# FlexiCan.net
KiCad netlist of a schematic drawn in Altium Designer
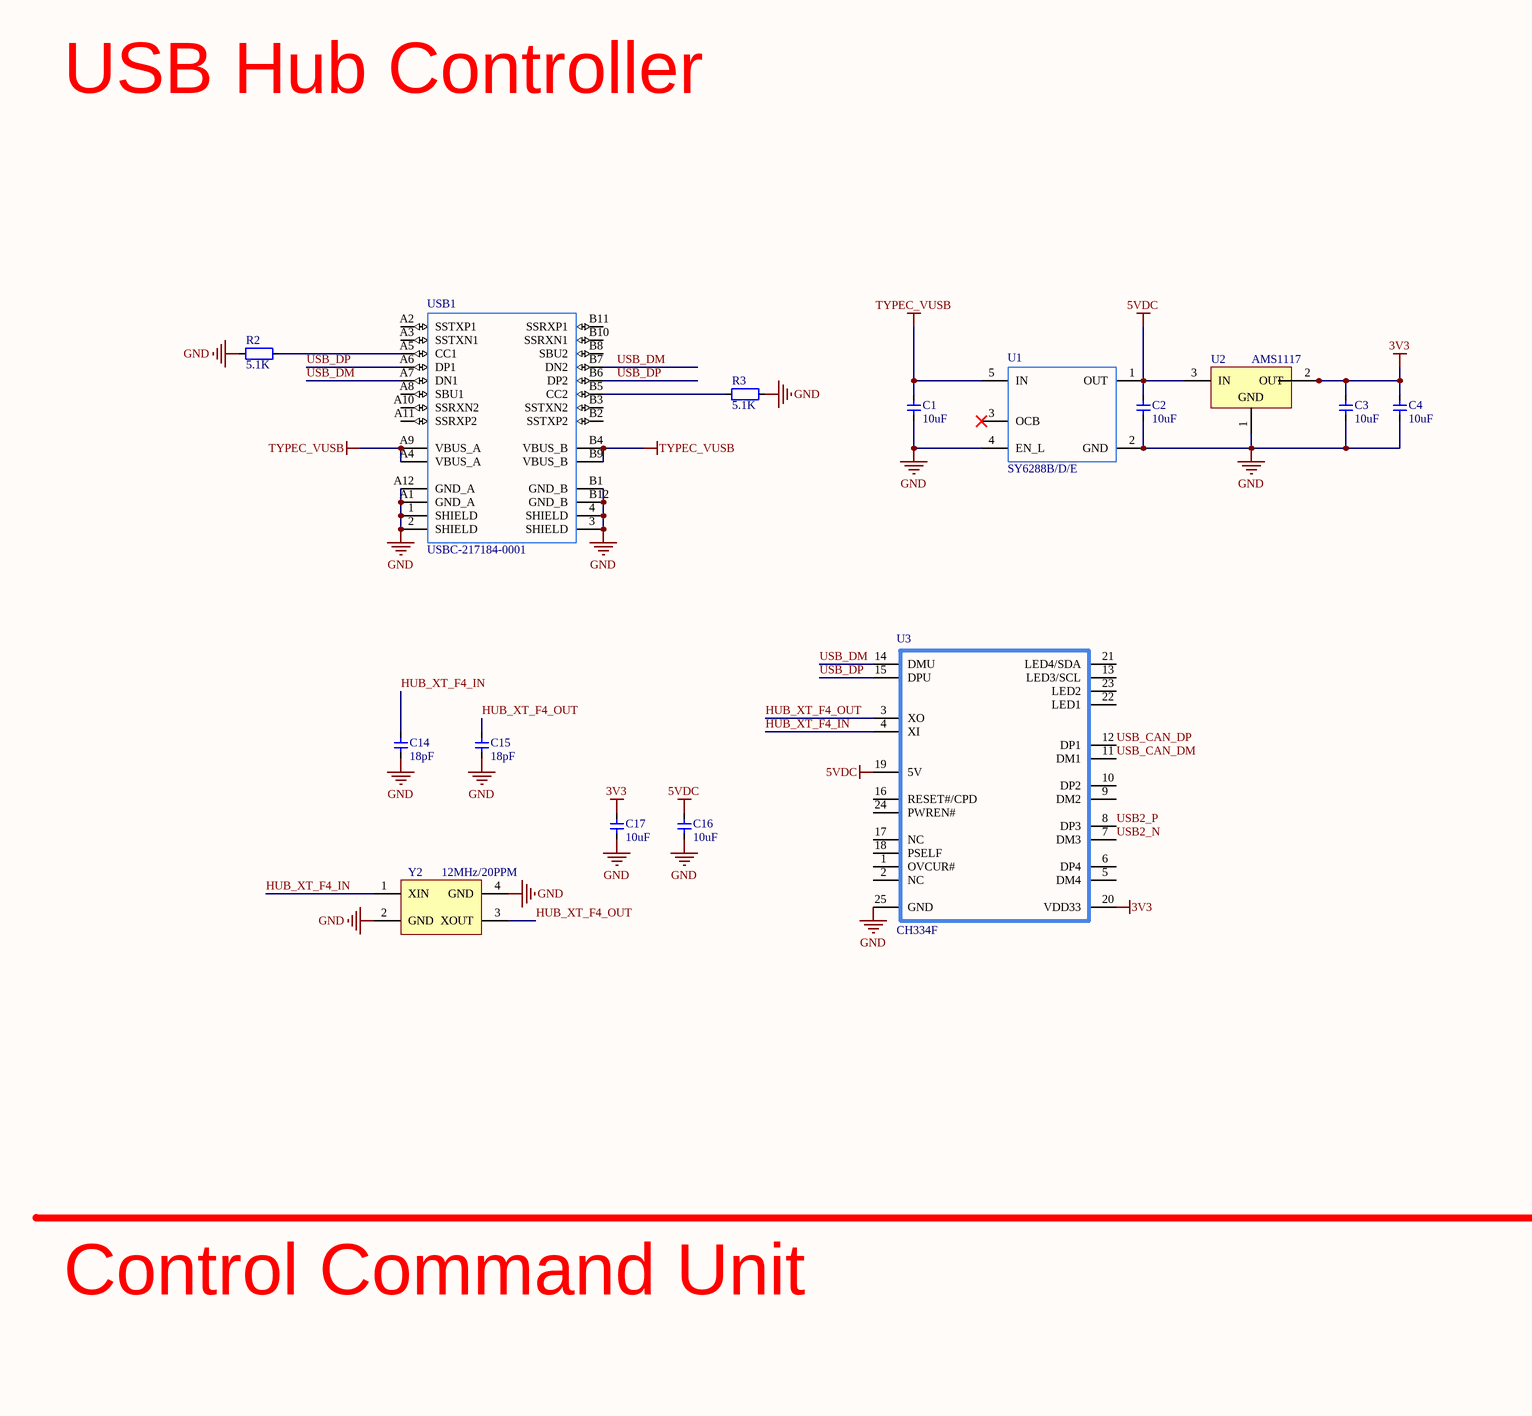
[diagram p0: FlexiCan.SchDoc, top left]
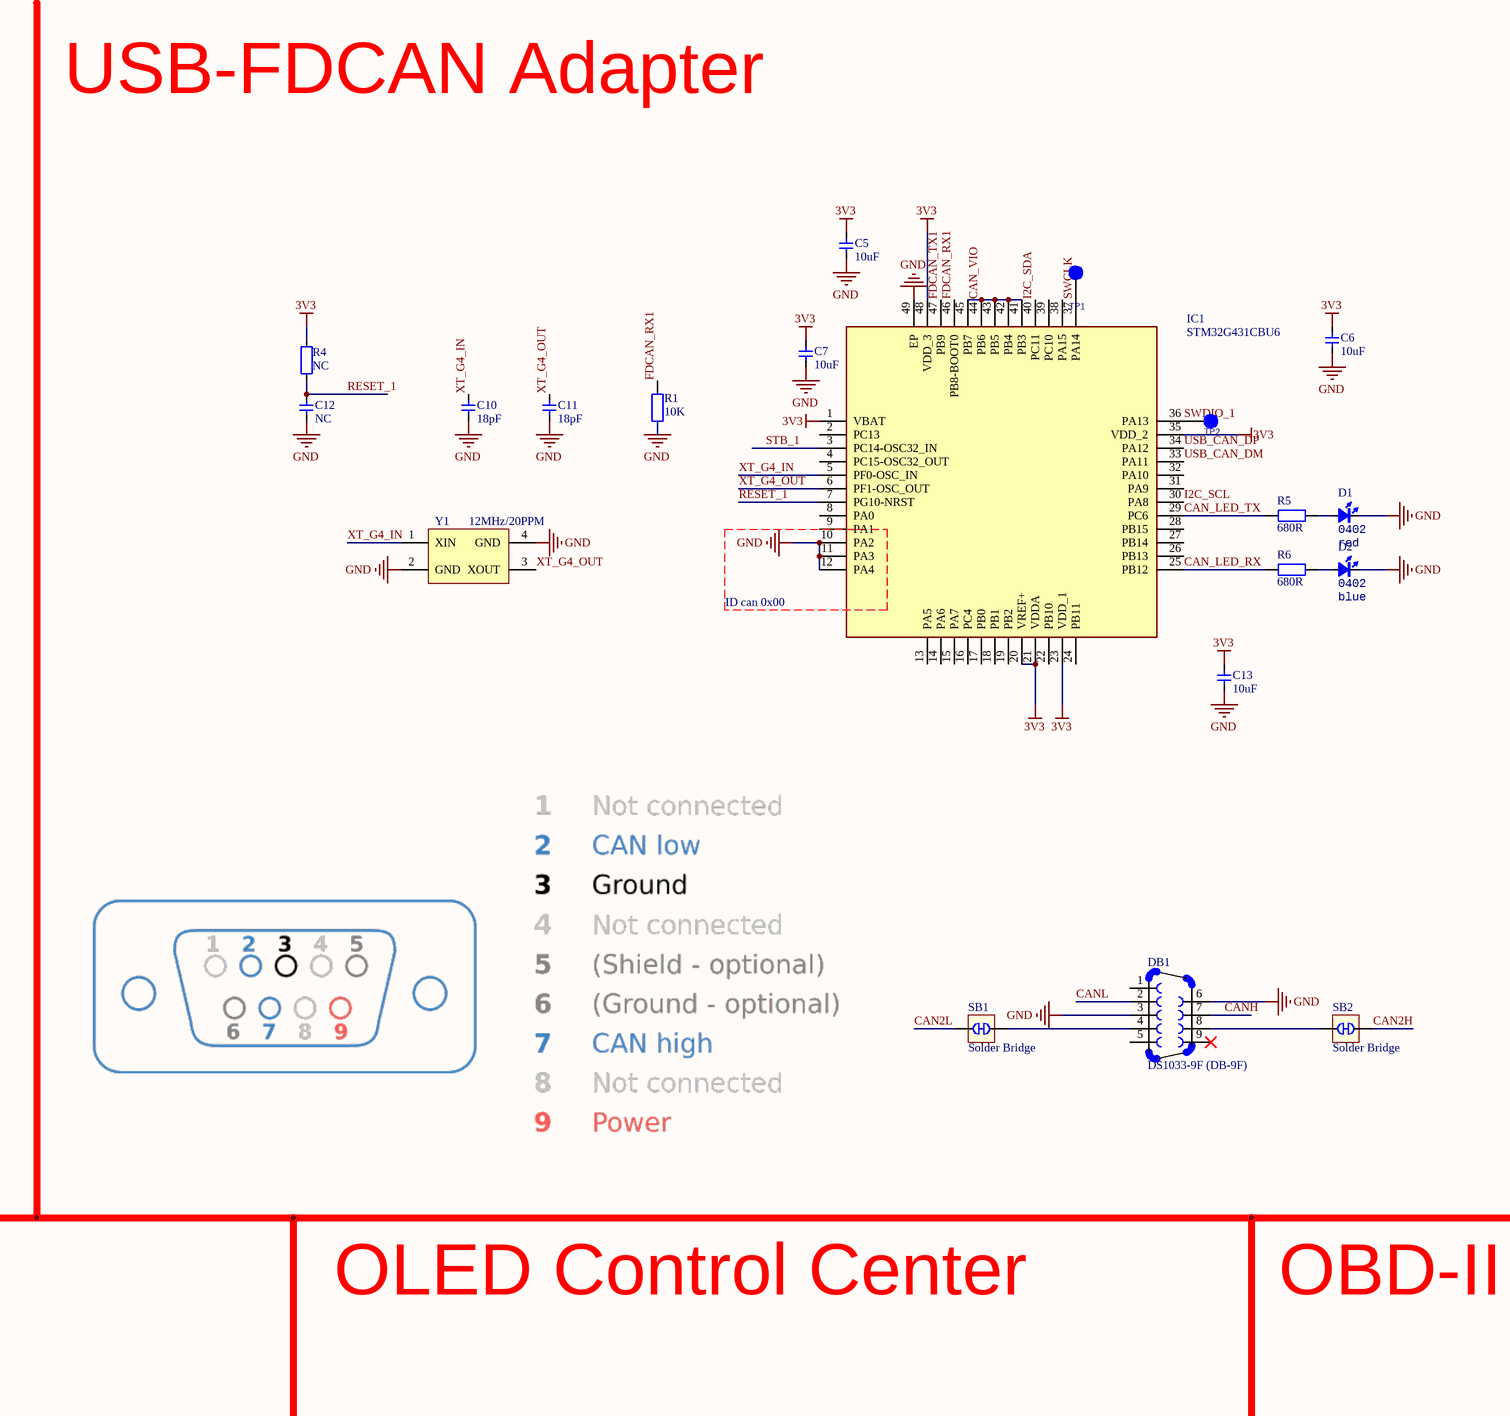
[diagram p1: FlexiCan.SchDoc, top middle]
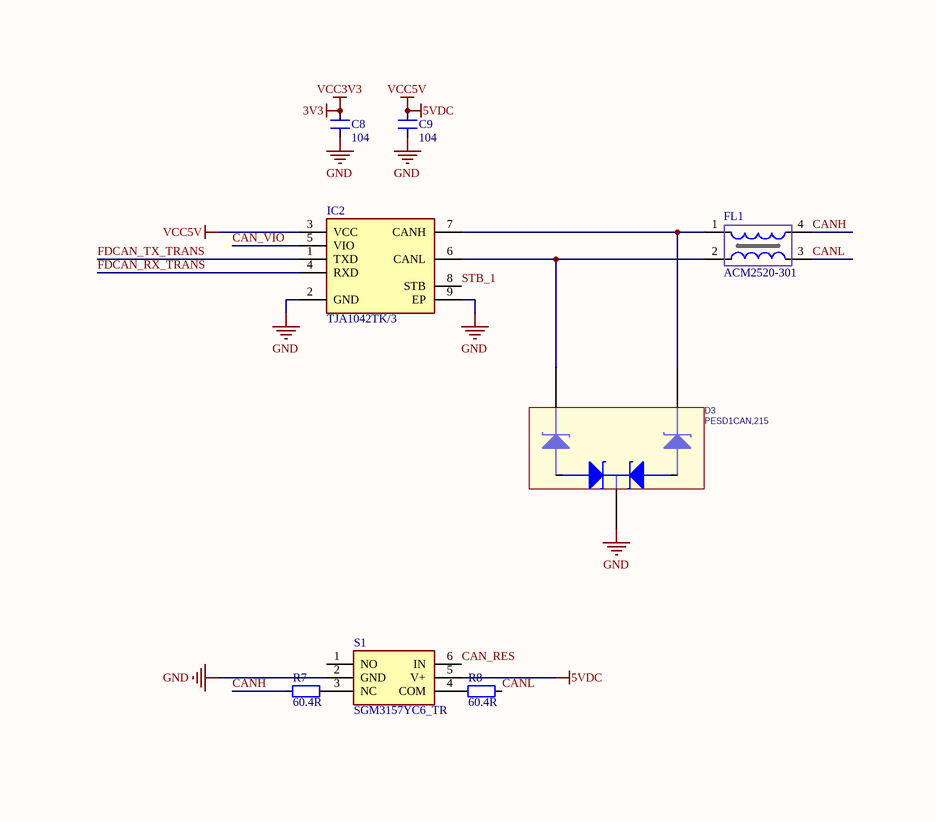
[diagram p2: FlexiCan.SchDoc, top right]
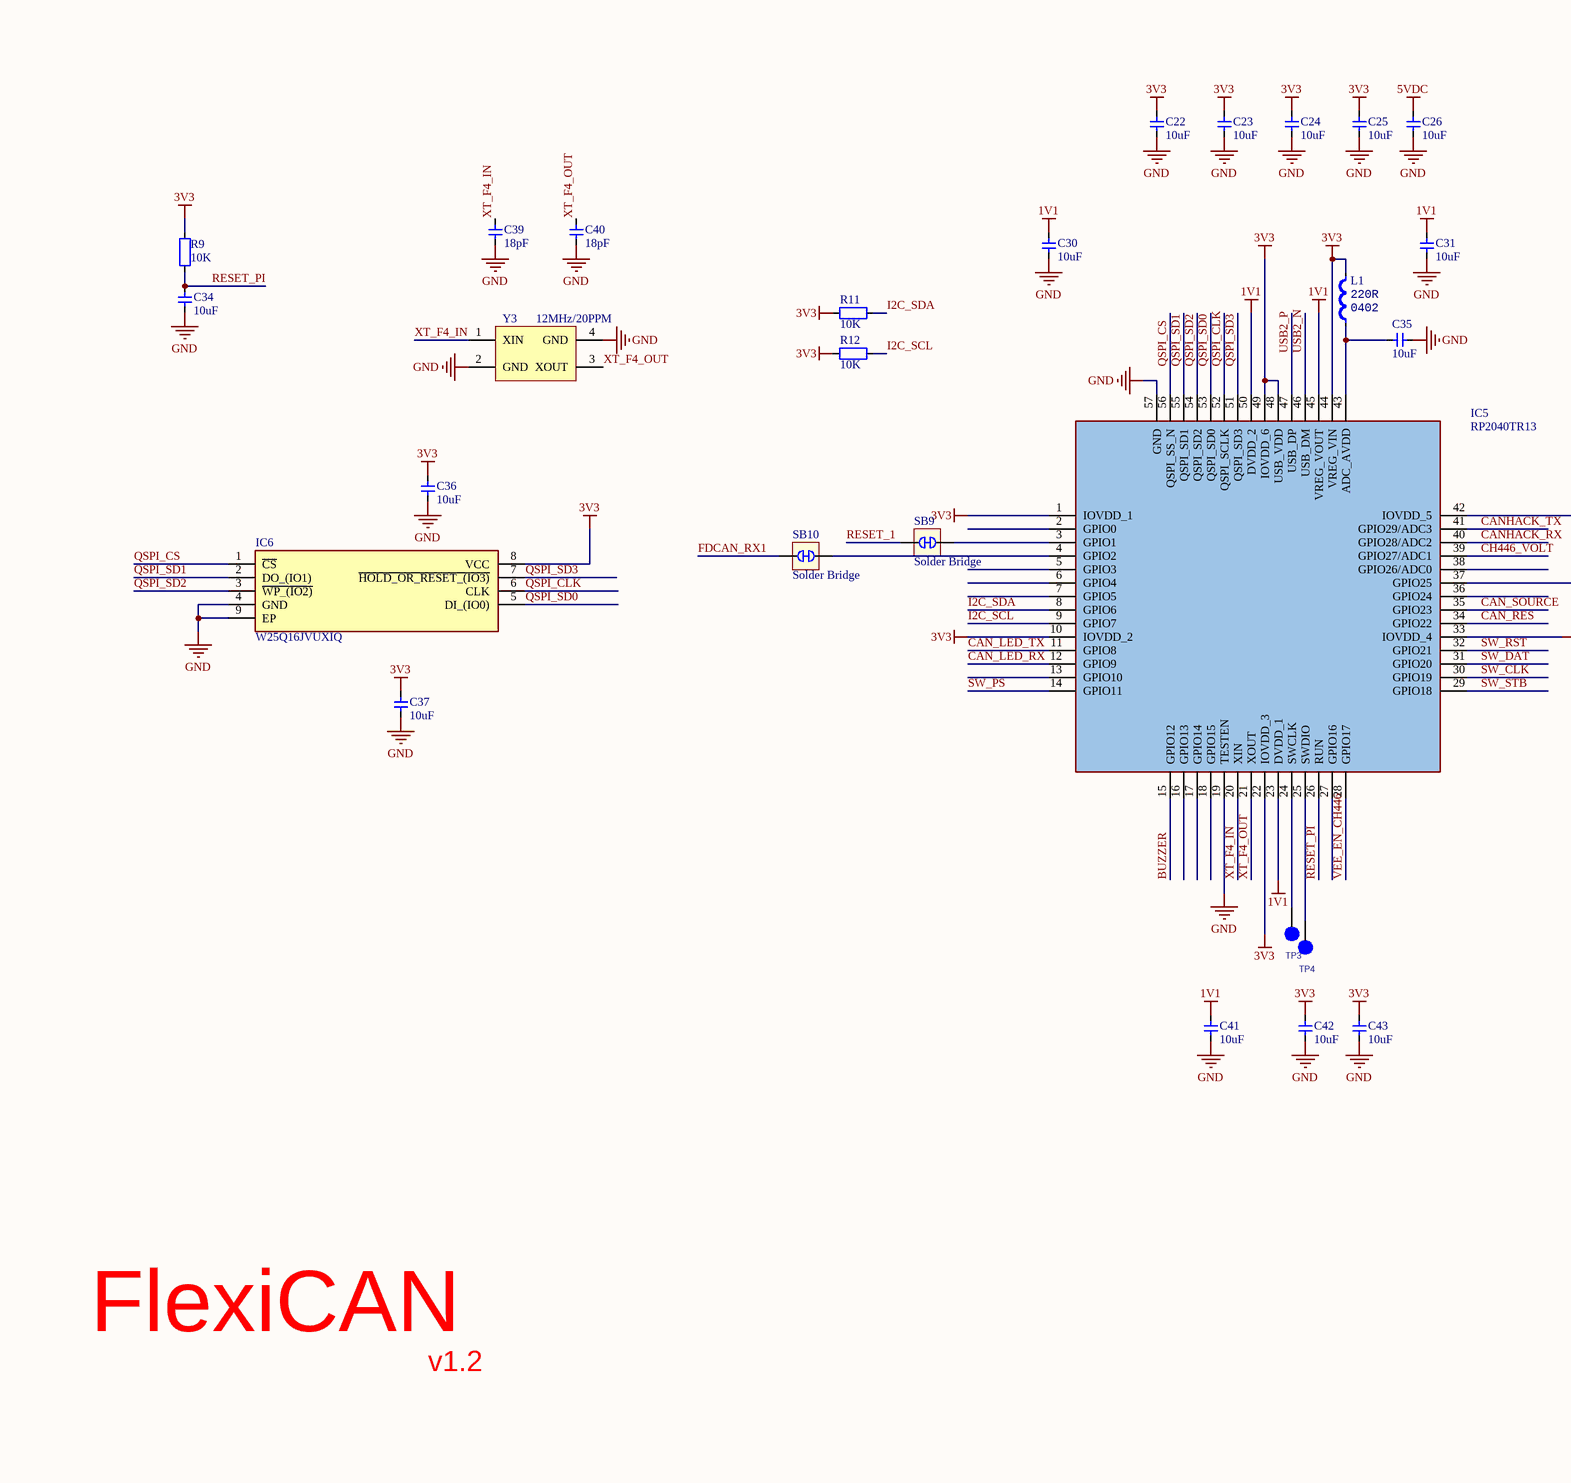
[diagram p3: FlexiCan.SchDoc, bottom left]
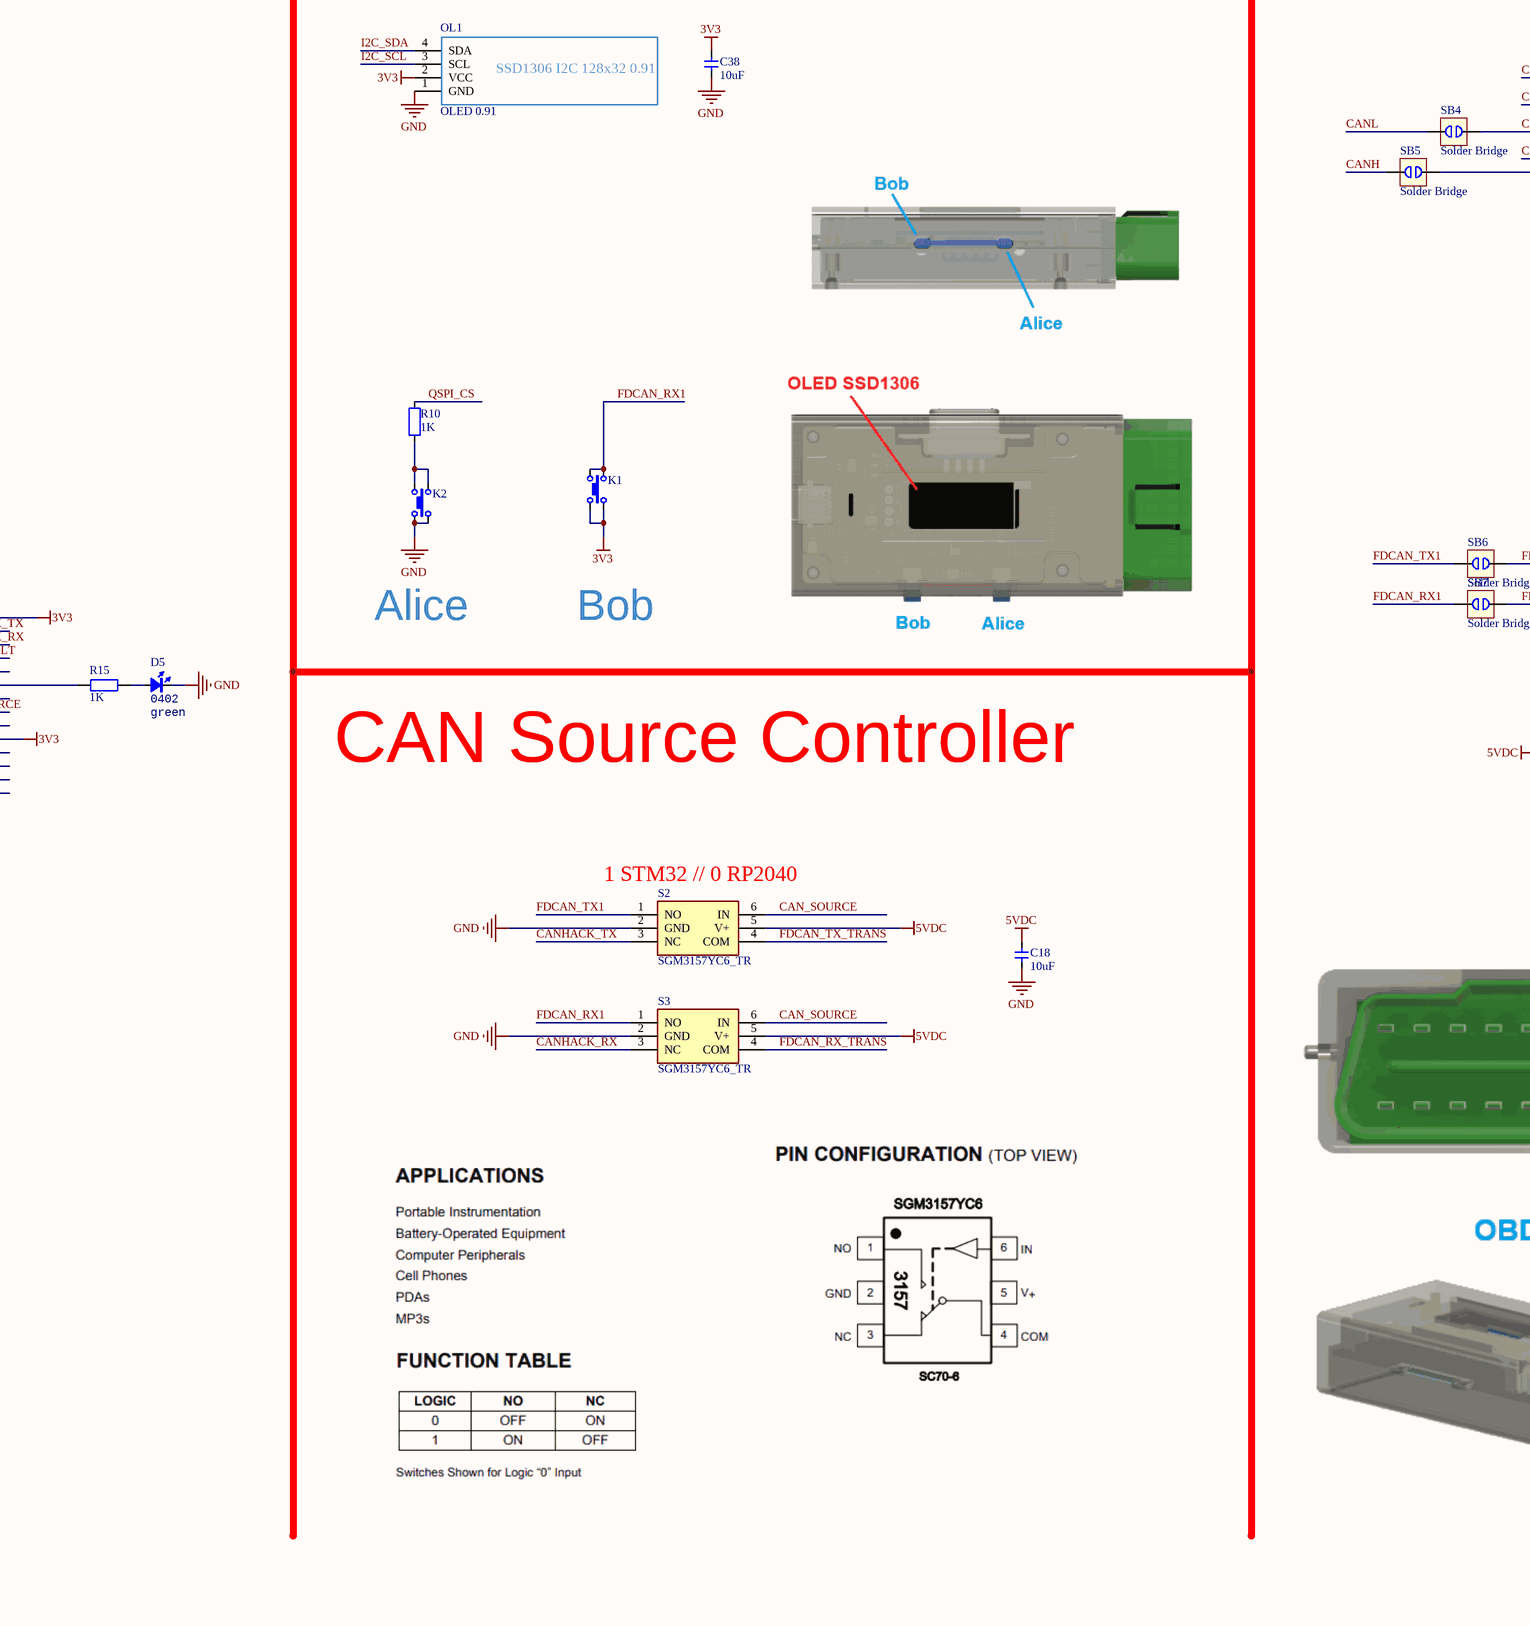
[diagram p4: FlexiCan.SchDoc, bottom middle]
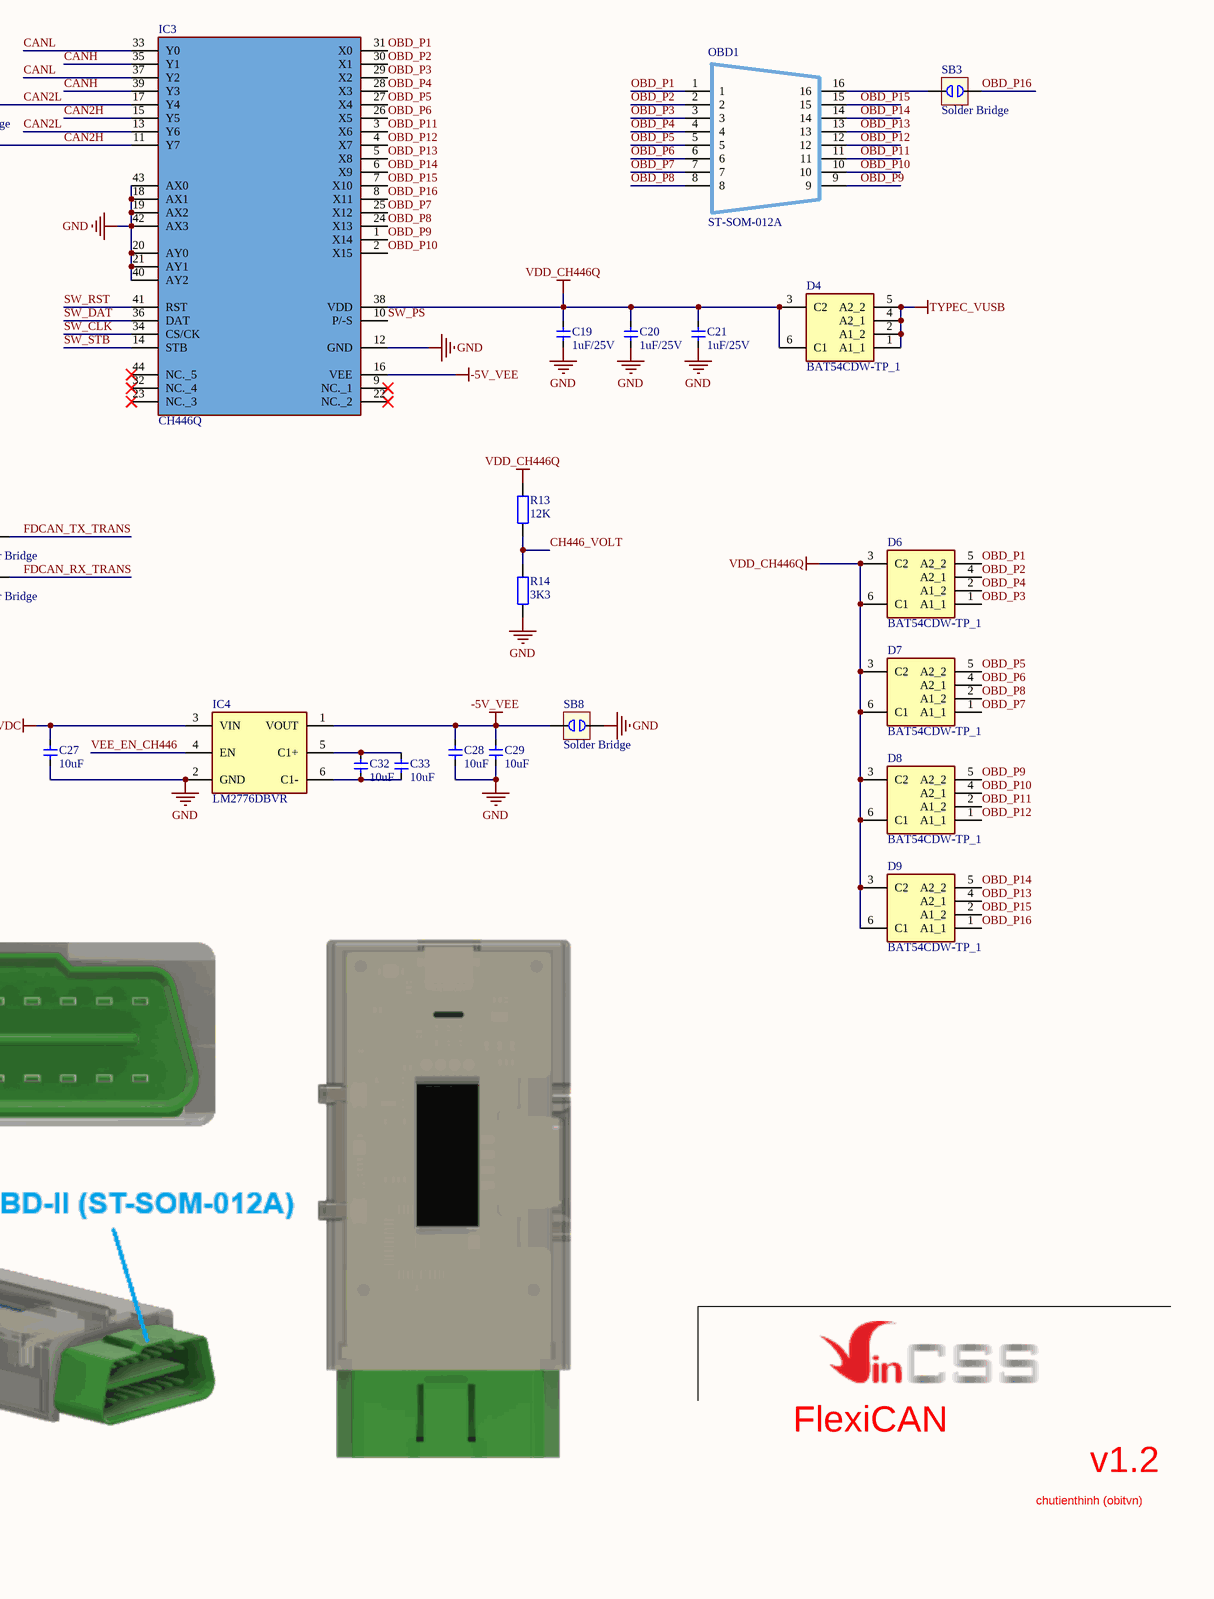
[diagram p5: FlexiCan.SchDoc, bottom right]

(export (version "E")
  (design (tool "Eeschema 10.0.6"))
  (components
    (comp (ref "C1")
      (value "10uF")
      (footprint "CAP_0402")
      (description "Capacitor")
      (libsource (lib "OBIT_TESLA") (part "C_0402"))
    )
    (comp (ref "C2")
      (value "10uF")
      (footprint "CAP_0402")
      (description "Capacitor")
      (libsource (lib "OBIT_TESLA") (part "C_0402"))
    )
    (comp (ref "C3")
      (value "10uF")
      (footprint "CAP_0402")
      (description "Capacitor")
      (libsource (lib "OBIT_TESLA") (part "C_0402"))
    )
    (comp (ref "C4")
      (value "10uF")
      (footprint "CAP_0402")
      (description "Capacitor")
      (libsource (lib "OBIT_TESLA") (part "C_0402"))
    )
    (comp (ref "C5")
      (value "10uF")
      (footprint "CAP_0402")
      (description "Capacitor")
      (libsource (lib "OBIT_TESLA") (part "C_0402"))
    )
    (comp (ref "C6")
      (value "10uF")
      (footprint "CAP_0402")
      (description "Capacitor")
      (libsource (lib "OBIT_TESLA") (part "C_0402"))
    )
    (comp (ref "C7")
      (value "10uF")
      (footprint "CAP_0402")
      (description "Capacitor")
      (libsource (lib "OBIT_TESLA") (part "C_0402"))
    )
    (comp (ref "C8")
      (value "104")
      (footprint "CAP_0402")
      (description "Cap SMD")
      (libsource (lib "OBIT_TESLA") (part "CM"))
    )
    (comp (ref "C9")
      (value "104")
      (footprint "CAP_0402")
      (description "Cap SMD")
      (libsource (lib "OBIT_TESLA") (part "CM"))
    )
    (comp (ref "C10")
      (value "18pF")
      (footprint "CAP_0402")
      (description "Capacitor")
      (libsource (lib "OBIT_TESLA") (part "C_0402"))
    )
    (comp (ref "C11")
      (value "18pF")
      (footprint "CAP_0402")
      (description "Capacitor")
      (libsource (lib "OBIT_TESLA") (part "C_0402"))
    )
    (comp (ref "C12")
      (value "NC")
      (footprint "CAP_0402")
      (description "Capacitor")
      (libsource (lib "OBIT_TESLA") (part "C_0402"))
    )
    (comp (ref "C13")
      (value "10uF")
      (footprint "CAP_0402")
      (description "Capacitor")
      (libsource (lib "OBIT_TESLA") (part "C_0402"))
    )
    (comp (ref "C14")
      (value "18pF")
      (footprint "CAP_0402")
      (description "Capacitor")
      (libsource (lib "OBIT_TESLA") (part "C_0402"))
    )
    (comp (ref "C15")
      (value "18pF")
      (footprint "CAP_0402")
      (description "Capacitor")
      (libsource (lib "OBIT_TESLA") (part "C_0402"))
    )
    (comp (ref "C16")
      (value "10uF")
      (footprint "CAP_0402")
      (description "Capacitor")
      (libsource (lib "OBIT_TESLA") (part "C_0402"))
    )
    (comp (ref "C17")
      (value "10uF")
      (footprint "CAP_0402")
      (description "Capacitor")
      (libsource (lib "OBIT_TESLA") (part "C_0402"))
    )
    (comp (ref "C18")
      (value "10uF")
      (footprint "CAP_0402")
      (description "Capacitor")
      (libsource (lib "OBIT_TESLA") (part "C_0402"))
    )
    (comp (ref "C19")
      (value "1uF/25V")
      (footprint "CAP_0402")
      (description "Capacitor")
      (libsource (lib "OBIT_TESLA") (part "C_0402"))
    )
    (comp (ref "C20")
      (value "1uF/25V")
      (footprint "CAP_0402")
      (description "Capacitor")
      (libsource (lib "OBIT_TESLA") (part "C_0402"))
    )
    (comp (ref "C21")
      (value "1uF/25V")
      (footprint "CAP_0402")
      (description "Capacitor")
      (libsource (lib "OBIT_TESLA") (part "C_0402"))
    )
    (comp (ref "C22")
      (value "10uF")
      (footprint "CAP_0402")
      (description "Capacitor")
      (libsource (lib "OBIT_TESLA") (part "C_0402"))
    )
    (comp (ref "C23")
      (value "10uF")
      (footprint "CAP_0402")
      (description "Capacitor")
      (libsource (lib "OBIT_TESLA") (part "C_0402"))
    )
    (comp (ref "C24")
      (value "10uF")
      (footprint "CAP_0402")
      (description "Capacitor")
      (libsource (lib "OBIT_TESLA") (part "C_0402"))
    )
    (comp (ref "C25")
      (value "10uF")
      (footprint "CAP_0402")
      (description "Capacitor")
      (libsource (lib "OBIT_TESLA") (part "C_0402"))
    )
    (comp (ref "C26")
      (value "10uF")
      (footprint "CAP_0402")
      (description "Capacitor")
      (libsource (lib "OBIT_TESLA") (part "C_0402"))
    )
    (comp (ref "C27")
      (value "10uF")
      (footprint "CAP_0402")
      (description "Capacitor")
      (libsource (lib "OBIT_TESLA") (part "C_0402"))
    )
    (comp (ref "C28")
      (value "10uF")
      (footprint "CAP_0402")
      (description "Capacitor")
      (libsource (lib "OBIT_TESLA") (part "C_0402"))
    )
    (comp (ref "C29")
      (value "10uF")
      (footprint "CAP_0402")
      (description "Capacitor")
      (libsource (lib "OBIT_TESLA") (part "C_0402"))
    )
    (comp (ref "C30")
      (value "10uF")
      (footprint "CAP_0402")
      (description "Capacitor")
      (libsource (lib "OBIT_TESLA") (part "C_0402"))
    )
    (comp (ref "C31")
      (value "10uF")
      (footprint "CAP_0402")
      (description "Capacitor")
      (libsource (lib "OBIT_TESLA") (part "C_0402"))
    )
    (comp (ref "C32")
      (value "10uF")
      (footprint "CAP_0402")
      (description "Capacitor")
      (libsource (lib "OBIT_TESLA") (part "C_0402"))
    )
    (comp (ref "C33")
      (value "10uF")
      (footprint "CAP_0402")
      (description "Capacitor")
      (libsource (lib "OBIT_TESLA") (part "C_0402"))
    )
    (comp (ref "C34")
      (value "10uF")
      (footprint "CAP_0402")
      (description "Capacitor")
      (libsource (lib "OBIT_TESLA") (part "C_0402"))
    )
    (comp (ref "C35")
      (value "10uF")
      (footprint "CAP_0402")
      (description "Capacitor")
      (libsource (lib "OBIT_TESLA") (part "C_0402"))
    )
    (comp (ref "C36")
      (value "10uF")
      (footprint "CAP_0402")
      (description "Capacitor")
      (libsource (lib "OBIT_TESLA") (part "C_0402"))
    )
    (comp (ref "C37")
      (value "10uF")
      (footprint "CAP_0402")
      (description "Capacitor")
      (libsource (lib "OBIT_TESLA") (part "C_0402"))
    )
    (comp (ref "C38")
      (value "10uF")
      (footprint "CAP_0402")
      (description "Capacitor")
      (libsource (lib "OBIT_TESLA") (part "C_0402"))
    )
    (comp (ref "C39")
      (value "18pF")
      (footprint "CAP_0402")
      (description "Capacitor")
      (libsource (lib "OBIT_TESLA") (part "C_0402"))
    )
    (comp (ref "C40")
      (value "18pF")
      (footprint "CAP_0402")
      (description "Capacitor")
      (libsource (lib "OBIT_TESLA") (part "C_0402"))
    )
    (comp (ref "C41")
      (value "10uF")
      (footprint "CAP_0402")
      (description "Capacitor")
      (libsource (lib "OBIT_TESLA") (part "C_0402"))
    )
    (comp (ref "C42")
      (value "10uF")
      (footprint "CAP_0402")
      (description "Capacitor")
      (libsource (lib "OBIT_TESLA") (part "C_0402"))
    )
    (comp (ref "C43")
      (value "10uF")
      (footprint "CAP_0402")
      (description "Capacitor")
      (libsource (lib "OBIT_TESLA") (part "C_0402"))
    )
    (comp (ref "D1")
      (value "red")
      (footprint "LED_0402_RED")
      (description "LED")
      (fields (field (name "TYPE") "0402"))
      (libsource (lib "OBIT_TESLA") (part "LED_0402"))
    )
    (comp (ref "D2")
      (value "blue")
      (footprint "LED_0402_BLUE")
      (description "LED")
      (fields (field (name "TYPE") "0402"))
      (libsource (lib "OBIT_TESLA") (part "LED_0402"))
    )
    (comp (ref "D3")
      (value "PESD1CAN,215")
      (footprint "SOT23-3")
      (description "TVS DIODE 5V 14V SOT23")
      (fields
        (field (name "MANUFACTURER PART #") "PESD5V0S2BT,215")
        (field (name "MANUFACTURER") "Nexperia USA Inc.")
        (field (name "CREATED BY") "eteofilo")
        (field (name "MODIFIED BY") "*")
      )
      (libsource (lib "OBIT_TESLA") (part "PESD5V0S2BT,215"))
    )
    (comp (ref "D4")
      (value "BAT54CDW-TP_1")
      (footprint "SOT65P222X120-6N")
      (description "Schottky Diode")
      (fields
        (field (name "MANUFACTURER_PART_NUMBER") "BAT54CDW-TP")
        (field (name "MOUSER PART NUMBER") "833-BAT54CDW-TP")
      )
      (libsource (lib "OBIT_TESLA") (part "BAT54CDW-TP_1"))
    )
    (comp (ref "D5")
      (value "green")
      (footprint "LED_0402_GREEN")
      (description "LED")
      (fields (field (name "TYPE") "0402"))
      (libsource (lib "OBIT_TESLA") (part "LED_0402"))
    )
    (comp (ref "D6")
      (value "BAT54CDW-TP_1")
      (footprint "SOT65P222X120-6N")
      (description "Schottky Diode")
      (fields
        (field (name "MANUFACTURER_PART_NUMBER") "BAT54CDW-TP")
        (field (name "MOUSER PART NUMBER") "833-BAT54CDW-TP")
      )
      (libsource (lib "OBIT_TESLA") (part "BAT54CDW-TP_1"))
    )
    (comp (ref "D7")
      (value "BAT54CDW-TP_1")
      (footprint "SOT65P222X120-6N")
      (description "Schottky Diode")
      (fields
        (field (name "MANUFACTURER_PART_NUMBER") "BAT54CDW-TP")
        (field (name "MOUSER PART NUMBER") "833-BAT54CDW-TP")
      )
      (libsource (lib "OBIT_TESLA") (part "BAT54CDW-TP_1"))
    )
    (comp (ref "D8")
      (value "BAT54CDW-TP_1")
      (footprint "SOT65P222X120-6N")
      (description "Schottky Diode")
      (fields
        (field (name "MANUFACTURER_PART_NUMBER") "BAT54CDW-TP")
        (field (name "MOUSER PART NUMBER") "833-BAT54CDW-TP")
      )
      (libsource (lib "OBIT_TESLA") (part "BAT54CDW-TP_1"))
    )
    (comp (ref "D9")
      (value "BAT54CDW-TP_1")
      (footprint "SOT65P222X120-6N")
      (description "Schottky Diode")
      (fields
        (field (name "MANUFACTURER_PART_NUMBER") "BAT54CDW-TP")
        (field (name "MOUSER PART NUMBER") "833-BAT54CDW-TP")
      )
      (libsource (lib "OBIT_TESLA") (part "BAT54CDW-TP_1"))
    )
    (comp (ref "DB1")
      (value "DS1033-9F (DB-9F)")
      (footprint "DB-9 DS1033-9F")
      (description "DS1033-9F (DB-9F) Female")
      (libsource (lib "OBIT_TESLA") (part "DB9-F"))
    )
    (comp (ref "FL1")
      (value "ACM2520-301")
      (footprint "ACM25203012P")
      (description "Common Mode Filters")
      (fields
        (field (name "MANUFACTURER_PART_NUMBER") "ACM9070-701-2PL-TL01")
        (field (name "MOUSER PART NUMBER") "810-ACM90707012PLTL")
      )
      (libsource (lib "OBIT_TESLA") (part "ACM2520-301-2PL-TL01_1"))
    )
    (comp (ref "IC1")
      (value "STM32G431CBU6")
      (footprint "QFN50P700X700X65-49N-D")
      (description "Integrated Circuit")
      (fields (field (name "MOUSER PART NUMBER") "511-STM32G431CBU6"))
      (libsource (lib "OBIT_TESLA") (part "STM32G431CBU6"))
    )
    (comp (ref "IC2")
      (value "TJA1042TK/3")
      (footprint "SON65P300X300X100-9N")
      (fields
        (field (name "MANUFACTURER_PART_NUMBER") "TJA1044VTKZ")
        (field (name "MOUSER PART NUMBER") "771-TJA1044VTKZ")
      )
      (libsource (lib "OBIT_TESLA") (part "SIT1044QTK/3"))
    )
    (comp (ref "IC3")
      (value "CH446Q")
      (footprint "QFP80P1350X1350X150-44N")
      (description "Integrated Circuit")
      (libsource (lib "OBIT_TESLA") (part "CH446Q"))
    )
    (comp (ref "IC4")
      (value "LM2776DBVR")
      (footprint "SOT95P280X145-6N")
      (description "Integrated Circuit")
      (fields (field (name "MOUSER PART NUMBER") "595-LM2776DBVR"))
      (libsource (lib "OBIT_TESLA") (part "LM2776DBVR"))
    )
    (comp (ref "IC5")
      (value "RP2040TR13")
      (footprint "RP2040TR13")
      (description "Integrated Circuit")
      (libsource (lib "OBIT_TESLA") (part "RP2040TR13"))
    )
    (comp (ref "IC6")
      (value "W25Q16JVUXIQ")
      (footprint "SON50P300X200X60-9N")
      (description "Integrated Circuit")
      (libsource (lib "OBIT_TESLA") (part "W25Q16JVUXIQ"))
    )
    (comp (ref "K1")
      (value "TACT 4P")
      (footprint "ButtonTACT_3.5*3.55_90")
      (description "Button")
      (libsource (lib "OBIT_TESLA") (part "ButtonTACT"))
    )
    (comp (ref "K2")
      (value "TACT 4P")
      (footprint "ButtonTACT_3.5*3.55_90")
      (description "Button")
      (libsource (lib "OBIT_TESLA") (part "ButtonTACT"))
    )
    (comp (ref "L1")
      (value "220R")
      (footprint "IND_0402Q")
      (description "Inductor")
      (fields (field (name "TYPE") "0402") (field (name "Comment") "H0402"))
      (libsource (lib "OBIT_TESLA") (part "Ind_0402"))
    )
    (comp (ref "OBD1")
      (value "ST-SOM-012A")
      (footprint "ST-SOM-012A")
      (description "ST-SOM-012A OBD II Connector")
      (libsource (lib "OBIT_TESLA") (part "ST-SOM-012A"))
    )
    (comp (ref "OL1")
      (value "OLED 0.91")
      (footprint "OLED 0.91 I2C")
      (description "HS HS91L02W2C01 \r\nSSD1306 I2C 128x32 0.91 - Organic Light Emitting Diode Display Screen ROHS")
      (libsource (lib "OBIT_TESLA") (part "OLED 0.91 128*32"))
    )
    (comp (ref "R1")
      (value "10K")
      (footprint "RES_0402")
      (description "Resistor R1/4W")
      (libsource (lib "OBIT_TESLA") (part "R"))
    )
    (comp (ref "R2")
      (value "5.1K")
      (footprint "RES_0402")
      (description "Resistor")
      (libsource (lib "OBIT_TESLA") (part "R-0402"))
    )
    (comp (ref "R3")
      (value "5.1K")
      (footprint "RES_0402")
      (description "Resistor")
      (libsource (lib "") (part "R-0402_1"))
    )
    (comp (ref "R4")
      (value "NC")
      (footprint "RES_0402")
      (description "Resistor")
      (libsource (lib "") (part "R-0402_2"))
    )
    (comp (ref "R5")
      (value "680R")
      (footprint "RES_0402")
      (description "Resistor R1/4W")
      (libsource (lib "OBIT_TESLA") (part "R"))
    )
    (comp (ref "R6")
      (value "680R")
      (footprint "RES_0402")
      (description "Resistor R1/4W")
      (libsource (lib "OBIT_TESLA") (part "R"))
    )
    (comp (ref "R7")
      (value "60.4R")
      (footprint "RES_0402")
      (description "Resistor")
      (libsource (lib "OBIT_TESLA") (part "R-0402"))
    )
    (comp (ref "R8")
      (value "60.4R")
      (footprint "RES_0402")
      (description "Resistor")
      (libsource (lib "OBIT_TESLA") (part "R-0402"))
    )
    (comp (ref "R9")
      (value "10K")
      (footprint "RES_0402")
      (description "Resistor")
      (libsource (lib "") (part "R-0402_2"))
    )
    (comp (ref "R10")
      (value "1K")
      (footprint "RES_0402")
      (description "Resistor")
      (libsource (lib "") (part "R-0402_3"))
    )
    (comp (ref "R11")
      (value "10K")
      (footprint "RES_0402")
      (description "Resistor")
      (libsource (lib "") (part "R-0402_1"))
    )
    (comp (ref "R12")
      (value "10K")
      (footprint "RES_0402")
      (description "Resistor")
      (libsource (lib "") (part "R-0402_1"))
    )
    (comp (ref "R13")
      (value "12K")
      (footprint "RES_0402")
      (description "Resistor R1/4W")
      (libsource (lib "OBIT_TESLA") (part "R"))
    )
    (comp (ref "R14")
      (value "3K3")
      (footprint "RES_0402")
      (description "Resistor R1/4W")
      (libsource (lib "OBIT_TESLA") (part "R"))
    )
    (comp (ref "R15")
      (value "1K")
      (footprint "RES_0402")
      (description "Resistor R1/4W")
      (libsource (lib "OBIT_TESLA") (part "R"))
    )
    (comp (ref "S1")
      (value "SGM3157YC6_TR")
      (footprint "SOT65P230X110-6N")
      (description "Switch")
      (fields (field (name "MANUFACTURER_PART_NUMBER") "SGM3157YC6/TR"))
      (libsource (lib "OBIT_TESLA") (part "SGM3157YC6_TR"))
    )
    (comp (ref "S2")
      (value "SGM3157YC6_TR")
      (footprint "SOT65P230X110-6N")
      (description "Switch")
      (fields (field (name "MANUFACTURER_PART_NUMBER") "SGM3157YC6/TR"))
      (libsource (lib "OBIT_TESLA") (part "SGM3157YC6_TR"))
    )
    (comp (ref "S3")
      (value "SGM3157YC6_TR")
      (footprint "SOT65P230X110-6N")
      (description "Switch")
      (fields (field (name "MANUFACTURER_PART_NUMBER") "SGM3157YC6/TR"))
      (libsource (lib "OBIT_TESLA") (part "SGM3157YC6_TR"))
    )
    (comp (ref "SB1")
      (value "Solder Bridge")
      (footprint "SB2_NC")
      (description "Solder Bridge 2")
      (libsource (lib "BYTECH_HW_LIB_2019") (part "SB 2 NC"))
    )
    (comp (ref "SB2")
      (value "Solder Bridge")
      (footprint "SB2_NC")
      (description "Solder Bridge 2")
      (libsource (lib "BYTECH_HW_LIB_2019") (part "SB 2 NC"))
    )
    (comp (ref "SB3")
      (value "Solder Bridge")
      (footprint "SB2_NO")
      (description "Solder Bridge 2")
      (libsource (lib "BYTECH_HW_LIB_2019") (part "SB 2 NO"))
    )
    (comp (ref "SB4")
      (value "Solder Bridge")
      (footprint "SB2_NO")
      (description "Solder Bridge 2")
      (libsource (lib "BYTECH_HW_LIB_2019") (part "SB 2 NO"))
    )
    (comp (ref "SB5")
      (value "Solder Bridge")
      (footprint "SB2_NO")
      (description "Solder Bridge 2")
      (libsource (lib "BYTECH_HW_LIB_2019") (part "SB 2 NO"))
    )
    (comp (ref "SB6")
      (value "Solder Bridge")
      (footprint "SB2_NO")
      (description "Solder Bridge 2")
      (libsource (lib "BYTECH_HW_LIB_2019") (part "SB 2 NO"))
    )
    (comp (ref "SB7")
      (value "Solder Bridge")
      (footprint "SB2_NO")
      (description "Solder Bridge 2")
      (libsource (lib "BYTECH_HW_LIB_2019") (part "SB 2 NO"))
    )
    (comp (ref "SB8")
      (value "Solder Bridge")
      (footprint "SB2_NO")
      (description "Solder Bridge 2")
      (libsource (lib "BYTECH_HW_LIB_2019") (part "SB 2 NO"))
    )
    (comp (ref "SB9")
      (value "Solder Bridge")
      (footprint "SB2_NC")
      (description "Solder Bridge 2")
      (libsource (lib "BYTECH_HW_LIB_2019") (part "SB 2 NC"))
    )
    (comp (ref "SB10")
      (value "Solder Bridge")
      (footprint "SB2_NC")
      (description "Solder Bridge 2")
      (libsource (lib "BYTECH_HW_LIB_2019") (part "SB 2 NC"))
    )
    (comp (ref "TP1")
      (value "TP 1mm")
      (footprint "SMT Test Point")
      (description "PCB TEST POINT SMT 1mm")
      (fields (field (name "MODIFIED BY") "*") (field (name "CREATED BY") "gmoreno"))
      (libsource (lib "") (part "TP 1mm_1"))
    )
    (comp (ref "TP2")
      (value "TP 1mm")
      (footprint "SMT Test Point")
      (description "PCB TEST POINT SMT 1mm")
      (fields (field (name "MODIFIED BY") "*") (field (name "CREATED BY") "gmoreno"))
      (libsource (lib "") (part "TP 1mm_2"))
    )
    (comp (ref "TP3")
      (value "TP 1mm")
      (footprint "SMT Test Point")
      (description "PCB TEST POINT SMT 1mm")
      (fields (field (name "MODIFIED BY") "*") (field (name "CREATED BY") "gmoreno"))
      (libsource (lib "OBIT_TESLA") (part "TP 1mm"))
    )
    (comp (ref "TP4")
      (value "TP 1mm")
      (footprint "SMT Test Point")
      (description "PCB TEST POINT SMT 1mm")
      (fields (field (name "MODIFIED BY") "*") (field (name "CREATED BY") "gmoreno"))
      (libsource (lib "OBIT_TESLA") (part "TP 1mm"))
    )
    (comp (ref "U1")
      (value "SY6288B/D/E")
      (footprint "SOT95P285X130-5N")
      (description "SY6288B/D/E Active Low")
      (libsource (lib "OBIT_TESLA") (part "SY6288_EN_L"))
    )
    (comp (ref "U2") (value "AMS1117") (footprint "SOT223") (libsource (lib "OBIT_TESLA") (part "AMS117")))
    (comp (ref "U3")
      (value "CH334F")
      (footprint "QFN50P400X400X80-25N-D")
      (description "CH334F Hub USB\r\nC5187527")
      (fields (field (name "JLCPCB PART #") "C5187527"))
      (libsource (lib "OBIT_TESLA") (part "CH334F"))
    )
    (comp (ref "USB1")
      (value "USBC-217184-0001")
      (footprint "Molex_217184-0001")
      (fields (field (name "MP") "USB4080-03-A") (field (name "MF") "Global Connector Technology"))
      (libsource (lib "OBIT_TESLA") (part "USBC-217184-0001"))
    )
    (comp (ref "Y1")
      (value "12MHz/20PPM")
      (footprint "XT-2520")
      (description "XT-2520")
      (fields (field (name "MF") "ECS International") (field (name "MP") "ECS-3225S30-240-EN-TR"))
      (libsource (lib "OBIT_TESLA") (part "XT-4Pin"))
    )
    (comp (ref "Y2")
      (value "12MHz/20PPM")
      (footprint "XT-2520")
      (description "XT-2520")
      (fields (field (name "MF") "ECS International") (field (name "MP") "ECS-3225S30-240-EN-TR"))
      (libsource (lib "OBIT_TESLA") (part "XT-4Pin"))
    )
    (comp (ref "Y3")
      (value "12MHz/20PPM")
      (footprint "XT-2520")
      (description "XT-2520")
      (fields (field (name "MF") "ECS International") (field (name "MP") "ECS-3225S30-240-EN-TR"))
      (libsource (lib "OBIT_TESLA") (part "XT-4Pin"))
    )
  )
  (nets
    (net (code "1") (name "-5V_VEE") (class "Default")
      (node (ref "C28") (pin "2") (pinfunction "2_2") (pintype "passive"))
      (node (ref "C29") (pin "2") (pinfunction "2_2") (pintype "passive"))
      (node (ref "IC3") (pin "16") (pinfunction "VEE_16") (pintype "passive"))
      (node (ref "IC4") (pin "1") (pinfunction "VOUT_1") (pintype "passive"))
      (node (ref "SB8") (pin "1") (pinfunction "1_1") (pintype "passive"))
    )
    (net (code "2") (name "/BUZZER") (class "Default")
      (node (ref "IC5") (pin "15") (pinfunction "GPIO12_15") (pintype "passive"))
    )
    (net (code "3") (name "/CAN2H") (class "Default")
      (node (ref "IC3") (pin "11") (pinfunction "Y7_11") (pintype "passive"))
      (node (ref "IC3") (pin "15") (pinfunction "Y5_15") (pintype "passive"))
      (node (ref "SB2") (pin "2") (pinfunction "2_2") (pintype "passive"))
      (node (ref "SB5") (pin "2") (pinfunction "2_2") (pintype "passive"))
    )
    (net (code "4") (name "/CAN2L") (class "Default")
      (node (ref "IC3") (pin "13") (pinfunction "Y6_13") (pintype "passive"))
      (node (ref "IC3") (pin "17") (pinfunction "Y4_17") (pintype "passive"))
      (node (ref "SB1") (pin "1") (pinfunction "1_1") (pintype "passive"))
      (node (ref "SB4") (pin "2") (pinfunction "2_2") (pintype "passive"))
    )
    (net (code "5") (name "/CANH") (class "Default")
      (node (ref "DB1") (pin "7") (pinfunction "7_7") (pintype "passive"))
      (node (ref "FL1") (pin "4") (pinfunction "4_4") (pintype "passive"))
      (node (ref "IC3") (pin "35") (pinfunction "Y1_35") (pintype "passive"))
      (node (ref "IC3") (pin "39") (pinfunction "Y3_39") (pintype "passive"))
      (node (ref "R7") (pin "1") (pinfunction "1_1") (pintype "passive"))
      (node (ref "SB5") (pin "1") (pinfunction "1_1") (pintype "passive"))
    )
    (net (code "6") (name "/CANHACK_RX") (class "Default")
      (node (ref "IC5") (pin "40") (pinfunction "GPIO28/ADC2_40") (pintype "passive"))
      (node (ref "S3") (pin "3") (pinfunction "NC_3") (pintype "passive"))
    )
    (net (code "7") (name "/CANHACK_TX") (class "Default")
      (node (ref "IC5") (pin "41") (pinfunction "GPIO29/ADC3_41") (pintype "passive"))
      (node (ref "S2") (pin "3") (pinfunction "NC_3") (pintype "passive"))
    )
    (net (code "8") (name "/CANL") (class "Default")
      (node (ref "DB1") (pin "2") (pinfunction "2_2") (pintype "passive"))
      (node (ref "FL1") (pin "3") (pinfunction "3_3") (pintype "passive"))
      (node (ref "IC3") (pin "33") (pinfunction "Y0_33") (pintype "passive"))
      (node (ref "IC3") (pin "37") (pinfunction "Y2_37") (pintype "passive"))
      (node (ref "R8") (pin "2") (pinfunction "2_2") (pintype "passive"))
      (node (ref "SB4") (pin "1") (pinfunction "1_1") (pintype "passive"))
    )
    (net (code "9") (name "/CAN_LED_RX") (class "Default")
      (node (ref "IC1") (pin "25") (pinfunction "PB12_25") (pintype "passive"))
      (node (ref "IC5") (pin "12") (pinfunction "GPIO9_12") (pintype "passive"))
      (node (ref "R6") (pin "1") (pinfunction "1_1") (pintype "passive"))
    )
    (net (code "10") (name "/CAN_LED_TX") (class "Default")
      (node (ref "IC1") (pin "29") (pinfunction "PC6_29") (pintype "passive"))
      (node (ref "IC5") (pin "11") (pinfunction "GPIO8_11") (pintype "passive"))
      (node (ref "R5") (pin "1") (pinfunction "1_1") (pintype "passive"))
    )
    (net (code "11") (name "/CAN_RES") (class "Default")
      (node (ref "IC5") (pin "34") (pinfunction "GPIO22_34") (pintype "passive"))
      (node (ref "S1") (pin "6") (pinfunction "IN_6") (pintype "passive"))
    )
    (net (code "12") (name "/CAN_SOURCE") (class "Default")
      (node (ref "IC5") (pin "35") (pinfunction "GPIO23_35") (pintype "passive"))
      (node (ref "S2") (pin "6") (pinfunction "IN_6") (pintype "passive"))
      (node (ref "S3") (pin "6") (pinfunction "IN_6") (pintype "passive"))
    )
    (net (code "13") (name "/CAN_VIO") (class "Default")
      (node (ref "IC1") (pin "41") (pinfunction "PB3_41") (pintype "passive"))
      (node (ref "IC1") (pin "42") (pinfunction "PB4_42") (pintype "passive"))
      (node (ref "IC1") (pin "43") (pinfunction "PB5_43") (pintype "passive"))
      (node (ref "IC1") (pin "44") (pinfunction "PB6_44") (pintype "passive"))
      (node (ref "IC1") (pin "45") (pinfunction "PB7_45") (pintype "passive"))
      (node (ref "IC2") (pin "5") (pinfunction "VIO_5") (pintype "passive"))
    )
    (net (code "14") (name "/CH446_VOLT") (class "Default")
      (node (ref "IC5") (pin "39") (pinfunction "GPIO27/ADC1_39") (pintype "passive"))
      (node (ref "R13") (pin "1") (pinfunction "1_1") (pintype "passive"))
      (node (ref "R14") (pin "2") (pinfunction "2_2") (pintype "passive"))
    )
    (net (code "15") (name "/FDCAN_RX1") (class "Default")
      (node (ref "IC1") (pin "46") (pinfunction "PB8-BOOT0_46") (pintype "passive"))
      (node (ref "K1") (pin "2") (pinfunction "2_2") (pintype "passive"))
      (node (ref "K1") (pin "4") (pinfunction "4_4") (pintype "passive"))
      (node (ref "R1") (pin "2") (pinfunction "2_2") (pintype "passive"))
      (node (ref "S3") (pin "1") (pinfunction "NO_1") (pintype "passive"))
      (node (ref "SB10") (pin "1") (pinfunction "1_1") (pintype "passive"))
      (node (ref "SB7") (pin "1") (pinfunction "1_1") (pintype "passive"))
    )
    (net (code "16") (name "/FDCAN_RX_TRANS") (class "Default")
      (node (ref "IC2") (pin "4") (pinfunction "RXD_4") (pintype "passive"))
      (node (ref "S3") (pin "4") (pinfunction "COM_4") (pintype "passive"))
      (node (ref "SB7") (pin "2") (pinfunction "2_2") (pintype "passive"))
    )
    (net (code "17") (name "/FDCAN_TX1") (class "Default")
      (node (ref "IC1") (pin "47") (pinfunction "PB9_47") (pintype "passive"))
      (node (ref "S2") (pin "1") (pinfunction "NO_1") (pintype "passive"))
      (node (ref "SB6") (pin "1") (pinfunction "1_1") (pintype "passive"))
    )
    (net (code "18") (name "/FDCAN_TX_TRANS") (class "Default")
      (node (ref "IC2") (pin "1") (pinfunction "TXD_1") (pintype "passive"))
      (node (ref "S2") (pin "4") (pinfunction "COM_4") (pintype "passive"))
      (node (ref "SB6") (pin "2") (pinfunction "2_2") (pintype "passive"))
    )
    (net (code "19") (name "/HUB_XT_F4_IN") (class "Default")
      (node (ref "C14") (pin "2") (pinfunction "2_2") (pintype "passive"))
      (node (ref "U3") (pin "4") (pinfunction "XI_4") (pintype "passive"))
      (node (ref "Y2") (pin "1") (pinfunction "XIN_1") (pintype "passive"))
    )
    (net (code "20") (name "/HUB_XT_F4_OUT") (class "Default")
      (node (ref "C15") (pin "2") (pinfunction "2_2") (pintype "passive"))
      (node (ref "U3") (pin "3") (pinfunction "XO_3") (pintype "passive"))
      (node (ref "Y2") (pin "3") (pinfunction "XOUT_3") (pintype "passive"))
    )
    (net (code "21") (name "/I2C_SCL") (class "Default")
      (node (ref "IC1") (pin "30") (pinfunction "PA8_30") (pintype "passive"))
      (node (ref "IC5") (pin "9") (pinfunction "GPIO7_9") (pintype "passive"))
      (node (ref "OL1") (pin "3") (pinfunction "SCL_3") (pintype "passive"))
      (node (ref "R12") (pin "1") (pinfunction "1_1") (pintype "passive"))
    )
    (net (code "22") (name "/I2C_SDA") (class "Default")
      (node (ref "IC1") (pin "40") (pinfunction "PC11_40") (pintype "passive"))
      (node (ref "IC5") (pin "8") (pinfunction "GPIO6_8") (pintype "passive"))
      (node (ref "OL1") (pin "4") (pinfunction "SDA_4") (pintype "passive"))
      (node (ref "R11") (pin "1") (pinfunction "1_1") (pintype "passive"))
    )
    (net (code "23") (name "/OBD_P1") (class "Default")
      (node (ref "D6") (pin "5") (pinfunction "A2_2_5") (pintype "passive"))
      (node (ref "IC3") (pin "31") (pinfunction "X0_31") (pintype "passive"))
      (node (ref "OBD1") (pin "1") (pinfunction "1_1") (pintype "passive"))
    )
    (net (code "24") (name "/OBD_P2") (class "Default")
      (node (ref "D6") (pin "4") (pinfunction "A2_1_4") (pintype "passive"))
      (node (ref "IC3") (pin "30") (pinfunction "X1_30") (pintype "passive"))
      (node (ref "OBD1") (pin "2") (pinfunction "2_2") (pintype "passive"))
    )
    (net (code "25") (name "/OBD_P3") (class "Default")
      (node (ref "D6") (pin "1") (pinfunction "A1_1_1") (pintype "passive"))
      (node (ref "IC3") (pin "29") (pinfunction "X2_29") (pintype "passive"))
      (node (ref "OBD1") (pin "3") (pinfunction "3_3") (pintype "passive"))
    )
    (net (code "26") (name "/OBD_P4") (class "Default")
      (node (ref "D6") (pin "2") (pinfunction "A1_2_2") (pintype "passive"))
      (node (ref "IC3") (pin "28") (pinfunction "X3_28") (pintype "passive"))
      (node (ref "OBD1") (pin "4") (pinfunction "4_4") (pintype "passive"))
    )
    (net (code "27") (name "/OBD_P5") (class "Default")
      (node (ref "D7") (pin "5") (pinfunction "A2_2_5") (pintype "passive"))
      (node (ref "IC3") (pin "27") (pinfunction "X4_27") (pintype "passive"))
      (node (ref "OBD1") (pin "5") (pinfunction "5_5") (pintype "passive"))
    )
    (net (code "28") (name "/OBD_P6") (class "Default")
      (node (ref "D7") (pin "4") (pinfunction "A2_1_4") (pintype "passive"))
      (node (ref "IC3") (pin "26") (pinfunction "X5_26") (pintype "passive"))
      (node (ref "OBD1") (pin "6") (pinfunction "6_6") (pintype "passive"))
    )
    (net (code "29") (name "/OBD_P7") (class "Default")
      (node (ref "D7") (pin "1") (pinfunction "A1_1_1") (pintype "passive"))
      (node (ref "IC3") (pin "25") (pinfunction "X12_25") (pintype "passive"))
      (node (ref "OBD1") (pin "7") (pinfunction "7_7") (pintype "passive"))
    )
    (net (code "30") (name "/OBD_P8") (class "Default")
      (node (ref "D7") (pin "2") (pinfunction "A1_2_2") (pintype "passive"))
      (node (ref "IC3") (pin "24") (pinfunction "X13_24") (pintype "passive"))
      (node (ref "OBD1") (pin "8") (pinfunction "8_8") (pintype "passive"))
    )
    (net (code "31") (name "/OBD_P9") (class "Default")
      (node (ref "D8") (pin "5") (pinfunction "A2_2_5") (pintype "passive"))
      (node (ref "IC3") (pin "1") (pinfunction "X14_1") (pintype "passive"))
      (node (ref "OBD1") (pin "9") (pinfunction "9_9") (pintype "passive"))
    )
    (net (code "32") (name "/OBD_P10") (class "Default")
      (node (ref "D8") (pin "4") (pinfunction "A2_1_4") (pintype "passive"))
      (node (ref "IC3") (pin "2") (pinfunction "X15_2") (pintype "passive"))
      (node (ref "OBD1") (pin "10") (pinfunction "10_10") (pintype "passive"))
    )
    (net (code "33") (name "/OBD_P11") (class "Default")
      (node (ref "D8") (pin "2") (pinfunction "A1_2_2") (pintype "passive"))
      (node (ref "IC3") (pin "3") (pinfunction "X6_3") (pintype "passive"))
      (node (ref "OBD1") (pin "11") (pinfunction "11_11") (pintype "passive"))
    )
    (net (code "34") (name "/OBD_P12") (class "Default")
      (node (ref "D8") (pin "1") (pinfunction "A1_1_1") (pintype "passive"))
      (node (ref "IC3") (pin "4") (pinfunction "X7_4") (pintype "passive"))
      (node (ref "OBD1") (pin "12") (pinfunction "12_12") (pintype "passive"))
    )
    (net (code "35") (name "/OBD_P13") (class "Default")
      (node (ref "D9") (pin "4") (pinfunction "A2_1_4") (pintype "passive"))
      (node (ref "IC3") (pin "5") (pinfunction "X8_5") (pintype "passive"))
      (node (ref "OBD1") (pin "13") (pinfunction "13_13") (pintype "passive"))
    )
    (net (code "36") (name "/OBD_P14") (class "Default")
      (node (ref "D9") (pin "5") (pinfunction "A2_2_5") (pintype "passive"))
      (node (ref "IC3") (pin "6") (pinfunction "X9_6") (pintype "passive"))
      (node (ref "OBD1") (pin "14") (pinfunction "14_14") (pintype "passive"))
    )
    (net (code "37") (name "/OBD_P15") (class "Default")
      (node (ref "D9") (pin "2") (pinfunction "A1_2_2") (pintype "passive"))
      (node (ref "IC3") (pin "7") (pinfunction "X10_7") (pintype "passive"))
      (node (ref "OBD1") (pin "15") (pinfunction "15_15") (pintype "passive"))
    )
    (net (code "38") (name "/OBD_P16") (class "Default")
      (node (ref "D9") (pin "1") (pinfunction "A1_1_1") (pintype "passive"))
      (node (ref "IC3") (pin "8") (pinfunction "X11_8") (pintype "passive"))
      (node (ref "SB3") (pin "2") (pinfunction "2_2") (pintype "passive"))
    )
    (net (code "39") (name "/QSPI_CLK") (class "Default")
      (node (ref "IC5") (pin "52") (pinfunction "QSPI_SCLK_52") (pintype "passive"))
      (node (ref "IC6") (pin "6") (pinfunction "CLK_6") (pintype "passive"))
    )
    (net (code "40") (name "/QSPI_CS") (class "Default")
      (node (ref "IC5") (pin "56") (pinfunction "QSPI_SS_N_56") (pintype "passive"))
      (node (ref "IC6") (pin "1") (pinfunction "~{CS}_1") (pintype "passive"))
      (node (ref "R10") (pin "1") (pinfunction "1_1") (pintype "passive"))
    )
    (net (code "41") (name "/QSPI_SD0") (class "Default")
      (node (ref "IC5") (pin "53") (pinfunction "QSPI_SD0_53") (pintype "passive"))
      (node (ref "IC6") (pin "5") (pinfunction "DI_(IO0)_5") (pintype "passive"))
    )
    (net (code "42") (name "/QSPI_SD1") (class "Default")
      (node (ref "IC5") (pin "55") (pinfunction "QSPI_SD1_55") (pintype "passive"))
      (node (ref "IC6") (pin "2") (pinfunction "DO_(IO1)_2") (pintype "passive"))
    )
    (net (code "43") (name "/QSPI_SD2") (class "Default")
      (node (ref "IC5") (pin "54") (pinfunction "QSPI_SD2_54") (pintype "passive"))
      (node (ref "IC6") (pin "3") (pinfunction "~{WP_(IO2)}_3") (pintype "passive"))
    )
    (net (code "44") (name "/QSPI_SD3") (class "Default")
      (node (ref "IC5") (pin "51") (pinfunction "QSPI_SD3_51") (pintype "passive"))
      (node (ref "IC6") (pin "7") (pinfunction "~{HOLD_OR_RESET_(IO3)}_7") (pintype "passive"))
    )
    (net (code "45") (name "/RESET_1") (class "Default")
      (node (ref "C12") (pin "2") (pinfunction "2_2") (pintype "passive"))
      (node (ref "IC1") (pin "7") (pinfunction "PG10-NRST_7") (pintype "passive"))
      (node (ref "R4") (pin "1") (pinfunction "1_1") (pintype "passive"))
      (node (ref "SB9") (pin "1") (pinfunction "1_1") (pintype "passive"))
    )
    (net (code "46") (name "/RESET_PI") (class "Default")
      (node (ref "C34") (pin "2") (pinfunction "2_2") (pintype "passive"))
      (node (ref "IC5") (pin "26") (pinfunction "RUN_26") (pintype "passive"))
      (node (ref "R9") (pin "1") (pinfunction "1_1") (pintype "passive"))
    )
    (net (code "47") (name "/STB_1") (class "Default")
      (node (ref "IC1") (pin "3") (pinfunction "PC14-OSC32_IN_3") (pintype "passive"))
      (node (ref "IC2") (pin "8") (pinfunction "STB_8") (pintype "passive"))
    )
    (net (code "48") (name "/SWCLK") (class "Default")
      (node (ref "IC1") (pin "37") (pinfunction "PA14_37") (pintype "passive"))
      (node (ref "TP1") (pin "1") (pinfunction "TP_1") (pintype "passive"))
    )
    (net (code "49") (name "/SWDIO_1") (class "Default")
      (node (ref "IC1") (pin "36") (pinfunction "PA13_36") (pintype "passive"))
      (node (ref "TP2") (pin "1") (pinfunction "TP_1") (pintype "passive"))
    )
    (net (code "50") (name "/SW_CLK") (class "Default")
      (node (ref "IC3") (pin "34") (pinfunction "CS/CK_34") (pintype "passive"))
      (node (ref "IC5") (pin "30") (pinfunction "GPIO19_30") (pintype "passive"))
    )
    (net (code "51") (name "/SW_DAT") (class "Default")
      (node (ref "IC3") (pin "36") (pinfunction "DAT_36") (pintype "passive"))
      (node (ref "IC5") (pin "31") (pinfunction "GPIO20_31") (pintype "passive"))
    )
    (net (code "52") (name "/SW_PS") (class "Default")
      (node (ref "IC3") (pin "10") (pinfunction "P/-S_10") (pintype "passive"))
      (node (ref "IC5") (pin "14") (pinfunction "GPIO11_14") (pintype "passive"))
    )
    (net (code "53") (name "/SW_RST") (class "Default")
      (node (ref "IC3") (pin "41") (pinfunction "RST_41") (pintype "passive"))
      (node (ref "IC5") (pin "32") (pinfunction "GPIO21_32") (pintype "passive"))
    )
    (net (code "54") (name "/SW_STB") (class "Default")
      (node (ref "IC3") (pin "14") (pinfunction "STB_14") (pintype "passive"))
      (node (ref "IC5") (pin "29") (pinfunction "GPIO18_29") (pintype "passive"))
    )
    (net (code "55") (name "/USB2_N") (class "Default")
      (node (ref "IC5") (pin "46") (pinfunction "USB_DM_46") (pintype "passive"))
      (node (ref "U3") (pin "7") (pinfunction "DM3_7") (pintype "passive"))
    )
    (net (code "56") (name "/USB2_P") (class "Default")
      (node (ref "IC5") (pin "47") (pinfunction "USB_DP_47") (pintype "passive"))
      (node (ref "U3") (pin "8") (pinfunction "DP3_8") (pintype "passive"))
    )
    (net (code "57") (name "/USB_CAN_DM") (class "Default")
      (node (ref "IC1") (pin "33") (pinfunction "PA11_33") (pintype "passive"))
      (node (ref "U3") (pin "11") (pinfunction "DM1_11") (pintype "passive"))
    )
    (net (code "58") (name "/USB_CAN_DP") (class "Default")
      (node (ref "IC1") (pin "34") (pinfunction "PA12_34") (pintype "passive"))
      (node (ref "U3") (pin "12") (pinfunction "DP1_12") (pintype "passive"))
    )
    (net (code "59") (name "/USB_DM") (class "Default")
      (node (ref "U3") (pin "14") (pinfunction "DMU_14") (pintype "passive"))
      (node (ref "USB1") (pin "A7") (pinfunction "DN1_A7") (pintype "bidirectional"))
      (node (ref "USB1") (pin "B7") (pinfunction "DN2_B7") (pintype "bidirectional"))
    )
    (net (code "60") (name "/USB_DP") (class "Default")
      (node (ref "U3") (pin "15") (pinfunction "DPU_15") (pintype "passive"))
      (node (ref "USB1") (pin "A6") (pinfunction "DP1_A6") (pintype "bidirectional"))
      (node (ref "USB1") (pin "B6") (pinfunction "DP2_B6") (pintype "bidirectional"))
    )
    (net (code "61") (name "/VEE_EN_CH446") (class "Default")
      (node (ref "IC4") (pin "4") (pinfunction "EN_4") (pintype "passive"))
      (node (ref "IC5") (pin "28") (pinfunction "GPIO17_28") (pintype "passive"))
    )
    (net (code "62") (name "/XT_F4_IN") (class "Default")
      (node (ref "C39") (pin "2") (pinfunction "2_2") (pintype "passive"))
      (node (ref "IC5") (pin "20") (pinfunction "XIN_20") (pintype "passive"))
      (node (ref "Y3") (pin "1") (pinfunction "XIN_1") (pintype "passive"))
    )
    (net (code "63") (name "/XT_F4_OUT") (class "Default")
      (node (ref "C40") (pin "2") (pinfunction "2_2") (pintype "passive"))
      (node (ref "IC5") (pin "21") (pinfunction "XOUT_21") (pintype "passive"))
      (node (ref "Y3") (pin "3") (pinfunction "XOUT_3") (pintype "passive"))
    )
    (net (code "64") (name "/XT_G4_IN") (class "Default")
      (node (ref "C10") (pin "2") (pinfunction "2_2") (pintype "passive"))
      (node (ref "IC1") (pin "5") (pinfunction "PF0-OSC_IN_5") (pintype "passive"))
      (node (ref "Y1") (pin "1") (pinfunction "XIN_1") (pintype "passive"))
    )
    (net (code "65") (name "/XT_G4_OUT") (class "Default")
      (node (ref "C11") (pin "2") (pinfunction "2_2") (pintype "passive"))
      (node (ref "IC1") (pin "6") (pinfunction "PF1-OSC_OUT_6") (pintype "passive"))
      (node (ref "Y1") (pin "3") (pinfunction "XOUT_3") (pintype "passive"))
    )
    (net (code "66") (name "1V1") (class "Default")
      (node (ref "C30") (pin "2") (pinfunction "2_2") (pintype "passive"))
      (node (ref "C31") (pin "2") (pinfunction "2_2") (pintype "passive"))
      (node (ref "C41") (pin "2") (pinfunction "2_2") (pintype "passive"))
      (node (ref "IC5") (pin "23") (pinfunction "DVDD_1_23") (pintype "passive"))
      (node (ref "IC5") (pin "45") (pinfunction "VREG_VOUT_45") (pintype "passive"))
      (node (ref "IC5") (pin "50") (pinfunction "DVDD_2_50") (pintype "passive"))
    )
    (net (code "67") (name "3V3") (class "Default")
      (node (ref "C13") (pin "2") (pinfunction "2_2") (pintype "passive"))
      (node (ref "C17") (pin "2") (pinfunction "2_2") (pintype "passive"))
      (node (ref "C22") (pin "2") (pinfunction "2_2") (pintype "passive"))
      (node (ref "C23") (pin "2") (pinfunction "2_2") (pintype "passive"))
      (node (ref "C24") (pin "2") (pinfunction "2_2") (pintype "passive"))
      (node (ref "C25") (pin "2") (pinfunction "2_2") (pintype "passive"))
      (node (ref "C3") (pin "2") (pinfunction "2_2") (pintype "passive"))
      (node (ref "C36") (pin "1") (pinfunction "1_1") (pintype "passive"))
      (node (ref "C37") (pin "2") (pinfunction "2_2") (pintype "passive"))
      (node (ref "C38") (pin "2") (pinfunction "2_2") (pintype "passive"))
      (node (ref "C4") (pin "2") (pinfunction "2_2") (pintype "passive"))
      (node (ref "C42") (pin "2") (pinfunction "2_2") (pintype "passive"))
      (node (ref "C43") (pin "2") (pinfunction "2_2") (pintype "passive"))
      (node (ref "C5") (pin "2") (pinfunction "2_2") (pintype "passive"))
      (node (ref "C6") (pin "2") (pinfunction "2_2") (pintype "passive"))
      (node (ref "C7") (pin "2") (pinfunction "2_2") (pintype "passive"))
      (node (ref "C8") (pin "1") (pinfunction "1_1") (pintype "passive"))
      (node (ref "IC1") (pin "1") (pinfunction "VBAT_1") (pintype "passive"))
      (node (ref "IC1") (pin "20") (pinfunction "VREF+_20") (pintype "passive"))
      (node (ref "IC1") (pin "21") (pinfunction "VDDA_21") (pintype "passive"))
      (node (ref "IC1") (pin "23") (pinfunction "VDD_1_23") (pintype "passive"))
      (node (ref "IC1") (pin "35") (pinfunction "VDD_2_35") (pintype "passive"))
      (node (ref "IC1") (pin "48") (pinfunction "VDD_3_48") (pintype "passive"))
      (node (ref "IC5") (pin "1") (pinfunction "IOVDD_1_1") (pintype "passive"))
      (node (ref "IC5") (pin "10") (pinfunction "IOVDD_2_10") (pintype "passive"))
      (node (ref "IC5") (pin "22") (pinfunction "IOVDD_3_22") (pintype "passive"))
      (node (ref "IC5") (pin "33") (pinfunction "IOVDD_4_33") (pintype "passive"))
      (node (ref "IC5") (pin "42") (pinfunction "IOVDD_5_42") (pintype "passive"))
      (node (ref "IC5") (pin "44") (pinfunction "VREG_VIN_44") (pintype "passive"))
      (node (ref "IC5") (pin "48") (pinfunction "USB_VDD_48") (pintype "passive"))
      (node (ref "IC5") (pin "49") (pinfunction "IOVDD_6_49") (pintype "passive"))
      (node (ref "IC6") (pin "8") (pinfunction "VCC_8") (pintype "passive"))
      (node (ref "K1") (pin "1") (pinfunction "1_1") (pintype "passive"))
      (node (ref "K1") (pin "3") (pinfunction "3_3") (pintype "passive"))
      (node (ref "L1") (pin "2") (pinfunction "2_2") (pintype "passive"))
      (node (ref "OL1") (pin "2") (pinfunction "VCC_2") (pintype "passive"))
      (node (ref "R11") (pin "2") (pinfunction "2_2") (pintype "passive"))
      (node (ref "R12") (pin "2") (pinfunction "2_2") (pintype "passive"))
      (node (ref "R4") (pin "2") (pinfunction "2_2") (pintype "passive"))
      (node (ref "R9") (pin "2") (pinfunction "2_2") (pintype "passive"))
      (node (ref "U2") (pin "2") (pinfunction "OUT_2") (pintype "power_in"))
      (node (ref "U2") (pin "4") (pinfunction "4_4") (pintype "passive"))
      (node (ref "U3") (pin "20") (pinfunction "VDD33_20") (pintype "passive"))
    )
    (net (code "68") (name "5VDC") (class "Default")
      (node (ref "C16") (pin "2") (pinfunction "2_2") (pintype "passive"))
      (node (ref "C18") (pin "2") (pinfunction "2_2") (pintype "passive"))
      (node (ref "C2") (pin "2") (pinfunction "2_2") (pintype "passive"))
      (node (ref "C26") (pin "2") (pinfunction "2_2") (pintype "passive"))
      (node (ref "C27") (pin "2") (pinfunction "2_2") (pintype "passive"))
      (node (ref "C9") (pin "1") (pinfunction "1_1") (pintype "passive"))
      (node (ref "IC2") (pin "3") (pinfunction "VCC_3") (pintype "passive"))
      (node (ref "IC4") (pin "3") (pinfunction "VIN_3") (pintype "passive"))
      (node (ref "S1") (pin "5") (pinfunction "V+_5") (pintype "passive"))
      (node (ref "S2") (pin "5") (pinfunction "V+_5") (pintype "passive"))
      (node (ref "S3") (pin "5") (pinfunction "V+_5") (pintype "passive"))
      (node (ref "U1") (pin "1") (pinfunction "OUT_1") (pintype "passive"))
      (node (ref "U2") (pin "3") (pinfunction "IN_3") (pintype "power_in"))
      (node (ref "U3") (pin "19") (pinfunction "5V_19") (pintype "passive"))
    )
    (net (code "69") (name "GND") (class "Default")
      (node (ref "C1") (pin "1") (pinfunction "1_1") (pintype "passive"))
      (node (ref "C10") (pin "1") (pinfunction "1_1") (pintype "passive"))
      (node (ref "C11") (pin "1") (pinfunction "1_1") (pintype "passive"))
      (node (ref "C12") (pin "1") (pinfunction "1_1") (pintype "passive"))
      (node (ref "C13") (pin "1") (pinfunction "1_1") (pintype "passive"))
      (node (ref "C14") (pin "1") (pinfunction "1_1") (pintype "passive"))
      (node (ref "C15") (pin "1") (pinfunction "1_1") (pintype "passive"))
      (node (ref "C16") (pin "1") (pinfunction "1_1") (pintype "passive"))
      (node (ref "C17") (pin "1") (pinfunction "1_1") (pintype "passive"))
      (node (ref "C18") (pin "1") (pinfunction "1_1") (pintype "passive"))
      (node (ref "C19") (pin "1") (pinfunction "1_1") (pintype "passive"))
      (node (ref "C2") (pin "1") (pinfunction "1_1") (pintype "passive"))
      (node (ref "C20") (pin "1") (pinfunction "1_1") (pintype "passive"))
      (node (ref "C21") (pin "1") (pinfunction "1_1") (pintype "passive"))
      (node (ref "C22") (pin "1") (pinfunction "1_1") (pintype "passive"))
      (node (ref "C23") (pin "1") (pinfunction "1_1") (pintype "passive"))
      (node (ref "C24") (pin "1") (pinfunction "1_1") (pintype "passive"))
      (node (ref "C25") (pin "1") (pinfunction "1_1") (pintype "passive"))
      (node (ref "C26") (pin "1") (pinfunction "1_1") (pintype "passive"))
      (node (ref "C27") (pin "1") (pinfunction "1_1") (pintype "passive"))
      (node (ref "C28") (pin "1") (pinfunction "1_1") (pintype "passive"))
      (node (ref "C29") (pin "1") (pinfunction "1_1") (pintype "passive"))
      (node (ref "C3") (pin "1") (pinfunction "1_1") (pintype "passive"))
      (node (ref "C30") (pin "1") (pinfunction "1_1") (pintype "passive"))
      (node (ref "C31") (pin "1") (pinfunction "1_1") (pintype "passive"))
      (node (ref "C34") (pin "1") (pinfunction "1_1") (pintype "passive"))
      (node (ref "C35") (pin "1") (pinfunction "1_1") (pintype "passive"))
      (node (ref "C36") (pin "2") (pinfunction "2_2") (pintype "passive"))
      (node (ref "C37") (pin "1") (pinfunction "1_1") (pintype "passive"))
      (node (ref "C38") (pin "1") (pinfunction "1_1") (pintype "passive"))
      (node (ref "C39") (pin "1") (pinfunction "1_1") (pintype "passive"))
      (node (ref "C4") (pin "1") (pinfunction "1_1") (pintype "passive"))
      (node (ref "C40") (pin "1") (pinfunction "1_1") (pintype "passive"))
      (node (ref "C41") (pin "1") (pinfunction "1_1") (pintype "passive"))
      (node (ref "C42") (pin "1") (pinfunction "1_1") (pintype "passive"))
      (node (ref "C43") (pin "1") (pinfunction "1_1") (pintype "passive"))
      (node (ref "C5") (pin "1") (pinfunction "1_1") (pintype "passive"))
      (node (ref "C6") (pin "1") (pinfunction "1_1") (pintype "passive"))
      (node (ref "C7") (pin "1") (pinfunction "1_1") (pintype "passive"))
      (node (ref "C8") (pin "2") (pinfunction "2_2") (pintype "passive"))
      (node (ref "C9") (pin "2") (pinfunction "2_2") (pintype "passive"))
      (node (ref "D1") (pin "2") (pinfunction "K_2") (pintype "passive"))
      (node (ref "D2") (pin "2") (pinfunction "K_2") (pintype "passive"))
      (node (ref "D3") (pin "3") (pinfunction "DK_3") (pintype "passive"))
      (node (ref "D5") (pin "2") (pinfunction "K_2") (pintype "passive"))
      (node (ref "DB1") (pin "3") (pinfunction "3_3") (pintype "passive"))
      (node (ref "DB1") (pin "6") (pinfunction "6_6") (pintype "passive"))
      (node (ref "IC1") (pin "10") (pinfunction "PA2_10") (pintype "passive"))
      (node (ref "IC1") (pin "11") (pinfunction "PA3_11") (pintype "passive"))
      (node (ref "IC1") (pin "12") (pinfunction "PA4_12") (pintype "passive"))
      (node (ref "IC1") (pin "49") (pinfunction "EP_49") (pintype "passive"))
      (node (ref "IC2") (pin "2") (pinfunction "GND_2") (pintype "passive"))
      (node (ref "IC2") (pin "9") (pinfunction "EP_9") (pintype "passive"))
      (node (ref "IC3") (pin "12") (pinfunction "GND_12") (pintype "passive"))
      (node (ref "IC3") (pin "18") (pinfunction "AX1_18") (pintype "passive"))
      (node (ref "IC3") (pin "19") (pinfunction "AX2_19") (pintype "passive"))
      (node (ref "IC3") (pin "20") (pinfunction "AY0_20") (pintype "passive"))
      (node (ref "IC3") (pin "21") (pinfunction "AY1_21") (pintype "passive"))
      (node (ref "IC3") (pin "40") (pinfunction "AY2_40") (pintype "passive"))
      (node (ref "IC3") (pin "42") (pinfunction "AX3_42") (pintype "passive"))
      (node (ref "IC3") (pin "43") (pinfunction "AX0_43") (pintype "passive"))
      (node (ref "IC4") (pin "2") (pinfunction "GND_2") (pintype "passive"))
      (node (ref "IC5") (pin "19") (pinfunction "TESTEN_19") (pintype "passive"))
      (node (ref "IC5") (pin "57") (pinfunction "GND_57") (pintype "passive"))
      (node (ref "IC6") (pin "4") (pinfunction "GND_4") (pintype "passive"))
      (node (ref "IC6") (pin "9") (pinfunction "EP_9") (pintype "passive"))
      (node (ref "K2") (pin "1") (pinfunction "1_1") (pintype "passive"))
      (node (ref "K2") (pin "3") (pinfunction "3_3") (pintype "passive"))
      (node (ref "OL1") (pin "1") (pinfunction "GND_1") (pintype "passive"))
      (node (ref "R1") (pin "1") (pinfunction "1_1") (pintype "passive"))
      (node (ref "R14") (pin "1") (pinfunction "1_1") (pintype "passive"))
      (node (ref "R2") (pin "1") (pinfunction "1_1") (pintype "passive"))
      (node (ref "R3") (pin "1") (pinfunction "1_1") (pintype "passive"))
      (node (ref "S1") (pin "2") (pinfunction "GND_2") (pintype "passive"))
      (node (ref "S2") (pin "2") (pinfunction "GND_2") (pintype "passive"))
      (node (ref "S3") (pin "2") (pinfunction "GND_2") (pintype "passive"))
      (node (ref "SB8") (pin "2") (pinfunction "2_2") (pintype "passive"))
      (node (ref "U1") (pin "2") (pinfunction "GND_2") (pintype "passive"))
      (node (ref "U1") (pin "4") (pinfunction "EN_L_4") (pintype "passive"))
      (node (ref "U2") (pin "1") (pinfunction "GND_1") (pintype "power_in"))
      (node (ref "U3") (pin "25") (pinfunction "GND_25") (pintype "passive"))
      (node (ref "USB1") (pin "1") (pinfunction "SHIELD_1") (pintype "passive"))
      (node (ref "USB1") (pin "2") (pinfunction "SHIELD_2") (pintype "passive"))
      (node (ref "USB1") (pin "3") (pinfunction "SHIELD_3") (pintype "passive"))
      (node (ref "USB1") (pin "4") (pinfunction "SHIELD_4") (pintype "passive"))
      (node (ref "USB1") (pin "A1") (pinfunction "GND_A_A1") (pintype "power_in"))
      (node (ref "USB1") (pin "A12") (pinfunction "GND_A_A12") (pintype "power_in"))
      (node (ref "USB1") (pin "B1") (pinfunction "GND_B_B1") (pintype "power_in"))
      (node (ref "USB1") (pin "B12") (pinfunction "GND_B_B12") (pintype "power_in"))
      (node (ref "Y1") (pin "2") (pinfunction "GND_2") (pintype "passive"))
      (node (ref "Y1") (pin "4") (pinfunction "GND_4") (pintype "passive"))
      (node (ref "Y2") (pin "2") (pinfunction "GND_2") (pintype "passive"))
      (node (ref "Y2") (pin "4") (pinfunction "GND_4") (pintype "passive"))
      (node (ref "Y3") (pin "2") (pinfunction "GND_2") (pintype "passive"))
      (node (ref "Y3") (pin "4") (pinfunction "GND_4") (pintype "passive"))
    )
    (net (code "70") (name "Net-(D1-A)") (class "Default")
      (node (ref "D1") (pin "1") (pinfunction "A_1") (pintype "passive"))
      (node (ref "R5") (pin "2") (pinfunction "2_2") (pintype "passive"))
    )
    (net (code "71") (name "Net-(D2-A)") (class "Default")
      (node (ref "D2") (pin "1") (pinfunction "A_1") (pintype "passive"))
      (node (ref "R6") (pin "2") (pinfunction "2_2") (pintype "passive"))
    )
    (net (code "72") (name "Net-(D3-K1)") (class "Default")
      (node (ref "D3") (pin "1") (pinfunction "K1_1") (pintype "passive"))
      (node (ref "FL1") (pin "1") (pinfunction "1_1") (pintype "passive"))
      (node (ref "IC2") (pin "7") (pinfunction "CANH_7") (pintype "passive"))
    )
    (net (code "73") (name "Net-(D3-K2)") (class "Default")
      (node (ref "D3") (pin "2") (pinfunction "K2_2") (pintype "passive"))
      (node (ref "FL1") (pin "2") (pinfunction "2_2") (pintype "passive"))
      (node (ref "IC2") (pin "6") (pinfunction "CANL_6") (pintype "passive"))
    )
    (net (code "74") (name "Net-(D5-A)") (class "Default")
      (node (ref "D5") (pin "1") (pinfunction "A_1") (pintype "passive"))
      (node (ref "R15") (pin "2") (pinfunction "2_2") (pintype "passive"))
    )
    (net (code "75") (name "Net-(DB1-Pad4)") (class "Default")
      (node (ref "DB1") (pin "4") (pinfunction "4_4") (pintype "passive"))
      (node (ref "SB1") (pin "2") (pinfunction "2_2") (pintype "passive"))
    )
    (net (code "76") (name "Net-(DB1-Pad8)") (class "Default")
      (node (ref "DB1") (pin "8") (pinfunction "8_8") (pintype "passive"))
      (node (ref "SB2") (pin "1") (pinfunction "1_1") (pintype "passive"))
    )
    (net (code "77") (name "Net-(IC4-C1+)") (class "Default")
      (node (ref "C32") (pin "2") (pinfunction "2_2") (pintype "passive"))
      (node (ref "C33") (pin "2") (pinfunction "2_2") (pintype "passive"))
      (node (ref "IC4") (pin "5") (pinfunction "C1+_5") (pintype "passive"))
    )
    (net (code "78") (name "Net-(IC4-C1-)") (class "Default")
      (node (ref "C32") (pin "1") (pinfunction "1_1") (pintype "passive"))
      (node (ref "C33") (pin "1") (pinfunction "1_1") (pintype "passive"))
      (node (ref "IC4") (pin "6") (pinfunction "C1-_6") (pintype "passive"))
    )
    (net (code "79") (name "Net-(IC5-ADC_AVDD)") (class "Default")
      (node (ref "C35") (pin "2") (pinfunction "2_2") (pintype "passive"))
      (node (ref "IC5") (pin "43") (pinfunction "ADC_AVDD_43") (pintype "passive"))
      (node (ref "L1") (pin "1") (pinfunction "1_1") (pintype "passive"))
    )
    (net (code "80") (name "Net-(IC5-GPIO1)") (class "Default")
      (node (ref "IC5") (pin "3") (pinfunction "GPIO1_3") (pintype "passive"))
      (node (ref "SB9") (pin "2") (pinfunction "2_2") (pintype "passive"))
    )
    (net (code "81") (name "Net-(IC5-GPIO2)") (class "Default")
      (node (ref "IC5") (pin "4") (pinfunction "GPIO2_4") (pintype "passive"))
      (node (ref "SB10") (pin "2") (pinfunction "2_2") (pintype "passive"))
    )
    (net (code "82") (name "Net-(IC5-GPIO25)") (class "Default")
      (node (ref "IC5") (pin "37") (pinfunction "GPIO25_37") (pintype "passive"))
      (node (ref "R15") (pin "1") (pinfunction "1_1") (pintype "passive"))
    )
    (net (code "83") (name "Net-(IC5-SWCLK)") (class "Default")
      (node (ref "IC5") (pin "24") (pinfunction "SWCLK_24") (pintype "passive"))
      (node (ref "TP3") (pin "1") (pinfunction "TP_1") (pintype "passive"))
    )
    (net (code "84") (name "Net-(IC5-SWDIO)") (class "Default")
      (node (ref "IC5") (pin "25") (pinfunction "SWDIO_25") (pintype "passive"))
      (node (ref "TP4") (pin "1") (pinfunction "TP_1") (pintype "passive"))
    )
    (net (code "85") (name "Net-(K2-Pad2)") (class "Default")
      (node (ref "K2") (pin "2") (pinfunction "2_2") (pintype "passive"))
      (node (ref "K2") (pin "4") (pinfunction "4_4") (pintype "passive"))
      (node (ref "R10") (pin "2") (pinfunction "2_2") (pintype "passive"))
    )
    (net (code "86") (name "Net-(OBD1-Pad16)") (class "Default")
      (node (ref "OBD1") (pin "16") (pinfunction "16_16") (pintype "passive"))
      (node (ref "SB3") (pin "1") (pinfunction "1_1") (pintype "passive"))
    )
    (net (code "87") (name "Net-(S1-COM)") (class "Default")
      (node (ref "R8") (pin "1") (pinfunction "1_1") (pintype "passive"))
      (node (ref "S1") (pin "4") (pinfunction "COM_4") (pintype "passive"))
    )
    (net (code "88") (name "Net-(S1-NC)") (class "Default")
      (node (ref "R7") (pin "2") (pinfunction "2_2") (pintype "passive"))
      (node (ref "S1") (pin "3") (pinfunction "NC_3") (pintype "passive"))
    )
    (net (code "89") (name "Net-(USB1-CC1)") (class "Default")
      (node (ref "R2") (pin "2") (pinfunction "2_2") (pintype "passive"))
      (node (ref "USB1") (pin "A5") (pinfunction "CC1_A5") (pintype "bidirectional"))
    )
    (net (code "90") (name "Net-(USB1-CC2)") (class "Default")
      (node (ref "R3") (pin "2") (pinfunction "2_2") (pintype "passive"))
      (node (ref "USB1") (pin "B5") (pinfunction "CC2_B5") (pintype "bidirectional"))
    )
    (net (code "91") (name "TYPEC_VUSB") (class "Default")
      (node (ref "C1") (pin "2") (pinfunction "2_2") (pintype "passive"))
      (node (ref "D4") (pin "1") (pinfunction "A1_1_1") (pintype "passive"))
      (node (ref "D4") (pin "2") (pinfunction "A1_2_2") (pintype "passive"))
      (node (ref "D4") (pin "4") (pinfunction "A2_1_4") (pintype "passive"))
      (node (ref "D4") (pin "5") (pinfunction "A2_2_5") (pintype "passive"))
      (node (ref "U1") (pin "5") (pinfunction "IN_5") (pintype "passive"))
      (node (ref "USB1") (pin "A4") (pinfunction "VBUS_A_A4") (pintype "power_in"))
      (node (ref "USB1") (pin "A9") (pinfunction "VBUS_A_A9") (pintype "power_in"))
      (node (ref "USB1") (pin "B4") (pinfunction "VBUS_B_B4") (pintype "power_in"))
      (node (ref "USB1") (pin "B9") (pinfunction "VBUS_B_B9") (pintype "power_in"))
    )
    (net (code "92") (name "VDD_CH446Q") (class "Default")
      (node (ref "C19") (pin "2") (pinfunction "2_2") (pintype "passive"))
      (node (ref "C20") (pin "2") (pinfunction "2_2") (pintype "passive"))
      (node (ref "C21") (pin "2") (pinfunction "2_2") (pintype "passive"))
      (node (ref "D4") (pin "3") (pinfunction "C2_3") (pintype "passive"))
      (node (ref "D4") (pin "6") (pinfunction "C1_6") (pintype "passive"))
      (node (ref "D6") (pin "3") (pinfunction "C2_3") (pintype "passive"))
      (node (ref "D6") (pin "6") (pinfunction "C1_6") (pintype "passive"))
      (node (ref "D7") (pin "3") (pinfunction "C2_3") (pintype "passive"))
      (node (ref "D7") (pin "6") (pinfunction "C1_6") (pintype "passive"))
      (node (ref "D8") (pin "3") (pinfunction "C2_3") (pintype "passive"))
      (node (ref "D8") (pin "6") (pinfunction "C1_6") (pintype "passive"))
      (node (ref "D9") (pin "3") (pinfunction "C2_3") (pintype "passive"))
      (node (ref "D9") (pin "6") (pinfunction "C1_6") (pintype "passive"))
      (node (ref "IC3") (pin "38") (pinfunction "VDD_38") (pintype "passive"))
      (node (ref "R13") (pin "2") (pinfunction "2_2") (pintype "passive"))
    )
    (net (code "93") (name "unconnected-(DB1-Pad1)") (class "Default")
      (node (ref "DB1") (pin "1") (pinfunction "1_1") (pintype "passive"))
    )
    (net (code "94") (name "unconnected-(DB1-Pad5)") (class "Default")
      (node (ref "DB1") (pin "5") (pinfunction "5_5") (pintype "passive"))
    )
    (net (code "95") (name "unconnected-(DB1-Pad9)") (class "Default")
      (node (ref "DB1") (pin "9") (pinfunction "9_9") (pintype "passive+no_connect"))
    )
    (net (code "96") (name "unconnected-(IC1-PA0-Pad8)") (class "Default")
      (node (ref "IC1") (pin "8") (pinfunction "PA0_8") (pintype "passive"))
    )
    (net (code "97") (name "unconnected-(IC1-PA1-Pad9)") (class "Default")
      (node (ref "IC1") (pin "9") (pinfunction "PA1_9") (pintype "passive"))
    )
    (net (code "98") (name "unconnected-(IC1-PA5-Pad13)") (class "Default")
      (node (ref "IC1") (pin "13") (pinfunction "PA5_13") (pintype "passive"))
    )
    (net (code "99") (name "unconnected-(IC1-PA6-Pad14)") (class "Default")
      (node (ref "IC1") (pin "14") (pinfunction "PA6_14") (pintype "passive"))
    )
    (net (code "100") (name "unconnected-(IC1-PA7-Pad15)") (class "Default")
      (node (ref "IC1") (pin "15") (pinfunction "PA7_15") (pintype "passive"))
    )
    (net (code "101") (name "unconnected-(IC1-PA9-Pad31)") (class "Default")
      (node (ref "IC1") (pin "31") (pinfunction "PA9_31") (pintype "passive"))
    )
    (net (code "102") (name "unconnected-(IC1-PA10-Pad32)") (class "Default")
      (node (ref "IC1") (pin "32") (pinfunction "PA10_32") (pintype "passive"))
    )
    (net (code "103") (name "unconnected-(IC1-PA15-Pad38)") (class "Default")
      (node (ref "IC1") (pin "38") (pinfunction "PA15_38") (pintype "passive"))
    )
    (net (code "104") (name "unconnected-(IC1-PB0-Pad17)") (class "Default")
      (node (ref "IC1") (pin "17") (pinfunction "PB0_17") (pintype "passive"))
    )
    (net (code "105") (name "unconnected-(IC1-PB1-Pad18)") (class "Default")
      (node (ref "IC1") (pin "18") (pinfunction "PB1_18") (pintype "passive"))
    )
    (net (code "106") (name "unconnected-(IC1-PB2-Pad19)") (class "Default")
      (node (ref "IC1") (pin "19") (pinfunction "PB2_19") (pintype "passive"))
    )
    (net (code "107") (name "unconnected-(IC1-PB10-Pad22)") (class "Default")
      (node (ref "IC1") (pin "22") (pinfunction "PB10_22") (pintype "passive"))
    )
    (net (code "108") (name "unconnected-(IC1-PB11-Pad24)") (class "Default")
      (node (ref "IC1") (pin "24") (pinfunction "PB11_24") (pintype "passive"))
    )
    (net (code "109") (name "unconnected-(IC1-PB13-Pad26)") (class "Default")
      (node (ref "IC1") (pin "26") (pinfunction "PB13_26") (pintype "passive"))
    )
    (net (code "110") (name "unconnected-(IC1-PB14-Pad27)") (class "Default")
      (node (ref "IC1") (pin "27") (pinfunction "PB14_27") (pintype "passive"))
    )
    (net (code "111") (name "unconnected-(IC1-PB15-Pad28)") (class "Default")
      (node (ref "IC1") (pin "28") (pinfunction "PB15_28") (pintype "passive"))
    )
    (net (code "112") (name "unconnected-(IC1-PC4-Pad16)") (class "Default")
      (node (ref "IC1") (pin "16") (pinfunction "PC4_16") (pintype "passive"))
    )
    (net (code "113") (name "unconnected-(IC1-PC10-Pad39)") (class "Default")
      (node (ref "IC1") (pin "39") (pinfunction "PC10_39") (pintype "passive"))
    )
    (net (code "114") (name "unconnected-(IC1-PC13-Pad2)") (class "Default")
      (node (ref "IC1") (pin "2") (pinfunction "PC13_2") (pintype "passive"))
    )
    (net (code "115") (name "unconnected-(IC1-PC15-OSC32_OUT-Pad4)") (class "Default")
      (node (ref "IC1") (pin "4") (pinfunction "PC15-OSC32_OUT_4") (pintype "passive"))
    )
    (net (code "116") (name "unconnected-(IC3-NC._1-Pad9)") (class "Default")
      (node (ref "IC3") (pin "9") (pinfunction "NC._1_9") (pintype "passive+no_connect"))
    )
    (net (code "117") (name "unconnected-(IC3-NC._2-Pad22)") (class "Default")
      (node (ref "IC3") (pin "22") (pinfunction "NC._2_22") (pintype "passive+no_connect"))
    )
    (net (code "118") (name "unconnected-(IC3-NC._3-Pad23)") (class "Default")
      (node (ref "IC3") (pin "23") (pinfunction "NC._3_23") (pintype "passive+no_connect"))
    )
    (net (code "119") (name "unconnected-(IC3-NC._4-Pad32)") (class "Default")
      (node (ref "IC3") (pin "32") (pinfunction "NC._4_32") (pintype "passive+no_connect"))
    )
    (net (code "120") (name "unconnected-(IC3-NC._5-Pad44)") (class "Default")
      (node (ref "IC3") (pin "44") (pinfunction "NC._5_44") (pintype "passive+no_connect"))
    )
    (net (code "121") (name "unconnected-(IC5-GPIO0-Pad2)") (class "Default")
      (node (ref "IC5") (pin "2") (pinfunction "GPIO0_2") (pintype "passive"))
    )
    (net (code "122") (name "unconnected-(IC5-GPIO3-Pad5)") (class "Default")
      (node (ref "IC5") (pin "5") (pinfunction "GPIO3_5") (pintype "passive"))
    )
    (net (code "123") (name "unconnected-(IC5-GPIO4-Pad6)") (class "Default")
      (node (ref "IC5") (pin "6") (pinfunction "GPIO4_6") (pintype "passive"))
    )
    (net (code "124") (name "unconnected-(IC5-GPIO5-Pad7)") (class "Default")
      (node (ref "IC5") (pin "7") (pinfunction "GPIO5_7") (pintype "passive"))
    )
    (net (code "125") (name "unconnected-(IC5-GPIO10-Pad13)") (class "Default")
      (node (ref "IC5") (pin "13") (pinfunction "GPIO10_13") (pintype "passive"))
    )
    (net (code "126") (name "unconnected-(IC5-GPIO13-Pad16)") (class "Default")
      (node (ref "IC5") (pin "16") (pinfunction "GPIO13_16") (pintype "passive"))
    )
    (net (code "127") (name "unconnected-(IC5-GPIO14-Pad17)") (class "Default")
      (node (ref "IC5") (pin "17") (pinfunction "GPIO14_17") (pintype "passive"))
    )
    (net (code "128") (name "unconnected-(IC5-GPIO15-Pad18)") (class "Default")
      (node (ref "IC5") (pin "18") (pinfunction "GPIO15_18") (pintype "passive"))
    )
    (net (code "129") (name "unconnected-(IC5-GPIO16-Pad27)") (class "Default")
      (node (ref "IC5") (pin "27") (pinfunction "GPIO16_27") (pintype "passive"))
    )
    (net (code "130") (name "unconnected-(IC5-GPIO24-Pad36)") (class "Default")
      (node (ref "IC5") (pin "36") (pinfunction "GPIO24_36") (pintype "passive"))
    )
    (net (code "131") (name "unconnected-(IC5-GPIO26{slash}ADC0-Pad38)") (class "Default")
      (node (ref "IC5") (pin "38") (pinfunction "GPIO26/ADC0_38") (pintype "passive"))
    )
    (net (code "132") (name "unconnected-(S1-NO-Pad1)") (class "Default")
      (node (ref "S1") (pin "1") (pinfunction "NO_1") (pintype "passive"))
    )
    (net (code "133") (name "unconnected-(U1-OCB-Pad3)") (class "Default")
      (node (ref "U1") (pin "3") (pinfunction "OCB_3") (pintype "passive+no_connect"))
    )
    (net (code "134") (name "unconnected-(U3-DM2-Pad9)") (class "Default")
      (node (ref "U3") (pin "9") (pinfunction "DM2_9") (pintype "passive"))
    )
    (net (code "135") (name "unconnected-(U3-DM4-Pad5)") (class "Default")
      (node (ref "U3") (pin "5") (pinfunction "DM4_5") (pintype "passive"))
    )
    (net (code "136") (name "unconnected-(U3-DP2-Pad10)") (class "Default")
      (node (ref "U3") (pin "10") (pinfunction "DP2_10") (pintype "passive"))
    )
    (net (code "137") (name "unconnected-(U3-DP4-Pad6)") (class "Default")
      (node (ref "U3") (pin "6") (pinfunction "DP4_6") (pintype "passive"))
    )
    (net (code "138") (name "unconnected-(U3-LED1-Pad22)") (class "Default")
      (node (ref "U3") (pin "22") (pinfunction "LED1_22") (pintype "passive"))
    )
    (net (code "139") (name "unconnected-(U3-LED2-Pad23)") (class "Default")
      (node (ref "U3") (pin "23") (pinfunction "LED2_23") (pintype "passive"))
    )
    (net (code "140") (name "unconnected-(U3-LED3{slash}SCL-Pad13)") (class "Default")
      (node (ref "U3") (pin "13") (pinfunction "LED3/SCL_13") (pintype "passive"))
    )
    (net (code "141") (name "unconnected-(U3-LED4{slash}SDA-Pad21)") (class "Default")
      (node (ref "U3") (pin "21") (pinfunction "LED4/SDA_21") (pintype "passive"))
    )
    (net (code "142") (name "unconnected-(U3-NC-Pad2)") (class "Default")
      (node (ref "U3") (pin "2") (pinfunction "NC_2") (pintype "passive"))
    )
    (net (code "143") (name "unconnected-(U3-NC-Pad17)") (class "Default")
      (node (ref "U3") (pin "17") (pinfunction "NC_17") (pintype "passive"))
    )
    (net (code "144") (name "unconnected-(U3-OVCUR#-Pad1)") (class "Default")
      (node (ref "U3") (pin "1") (pinfunction "OVCUR#_1") (pintype "passive"))
    )
    (net (code "145") (name "unconnected-(U3-PSELF-Pad18)") (class "Default")
      (node (ref "U3") (pin "18") (pinfunction "PSELF_18") (pintype "passive"))
    )
    (net (code "146") (name "unconnected-(U3-PWREN#-Pad24)") (class "Default")
      (node (ref "U3") (pin "24") (pinfunction "PWREN#_24") (pintype "passive"))
    )
    (net (code "147") (name "unconnected-(U3-RESET#{slash}CPD-Pad16)") (class "Default")
      (node (ref "U3") (pin "16") (pinfunction "RESET#/CPD_16") (pintype "passive"))
    )
    (net (code "148") (name "unconnected-(USB1-SBU1-PadA8)") (class "Default")
      (node (ref "USB1") (pin "A8") (pinfunction "SBU1_A8") (pintype "bidirectional"))
    )
    (net (code "149") (name "unconnected-(USB1-SBU2-PadB8)") (class "Default")
      (node (ref "USB1") (pin "B8") (pinfunction "SBU2_B8") (pintype "bidirectional"))
    )
    (net (code "150") (name "unconnected-(USB1-SSRXN1-PadB10)") (class "Default")
      (node (ref "USB1") (pin "B10") (pinfunction "SSRXN1_B10") (pintype "bidirectional"))
    )
    (net (code "151") (name "unconnected-(USB1-SSRXN2-PadA10)") (class "Default")
      (node (ref "USB1") (pin "A10") (pinfunction "SSRXN2_A10") (pintype "bidirectional"))
    )
    (net (code "152") (name "unconnected-(USB1-SSRXP1-PadB11)") (class "Default")
      (node (ref "USB1") (pin "B11") (pinfunction "SSRXP1_B11") (pintype "bidirectional"))
    )
    (net (code "153") (name "unconnected-(USB1-SSRXP2-PadA11)") (class "Default")
      (node (ref "USB1") (pin "A11") (pinfunction "SSRXP2_A11") (pintype "bidirectional"))
    )
    (net (code "154") (name "unconnected-(USB1-SSTXN1-PadA3)") (class "Default")
      (node (ref "USB1") (pin "A3") (pinfunction "SSTXN1_A3") (pintype "bidirectional"))
    )
    (net (code "155") (name "unconnected-(USB1-SSTXN2-PadB3)") (class "Default")
      (node (ref "USB1") (pin "B3") (pinfunction "SSTXN2_B3") (pintype "bidirectional"))
    )
    (net (code "156") (name "unconnected-(USB1-SSTXP1-PadA2)") (class "Default")
      (node (ref "USB1") (pin "A2") (pinfunction "SSTXP1_A2") (pintype "bidirectional"))
    )
    (net (code "157") (name "unconnected-(USB1-SSTXP2-PadB2)") (class "Default")
      (node (ref "USB1") (pin "B2") (pinfunction "SSTXP2_B2") (pintype "bidirectional"))
    )
  )
)
